# BMW_variante.net
KiCad netlist of a schematic drawn in EAGLE
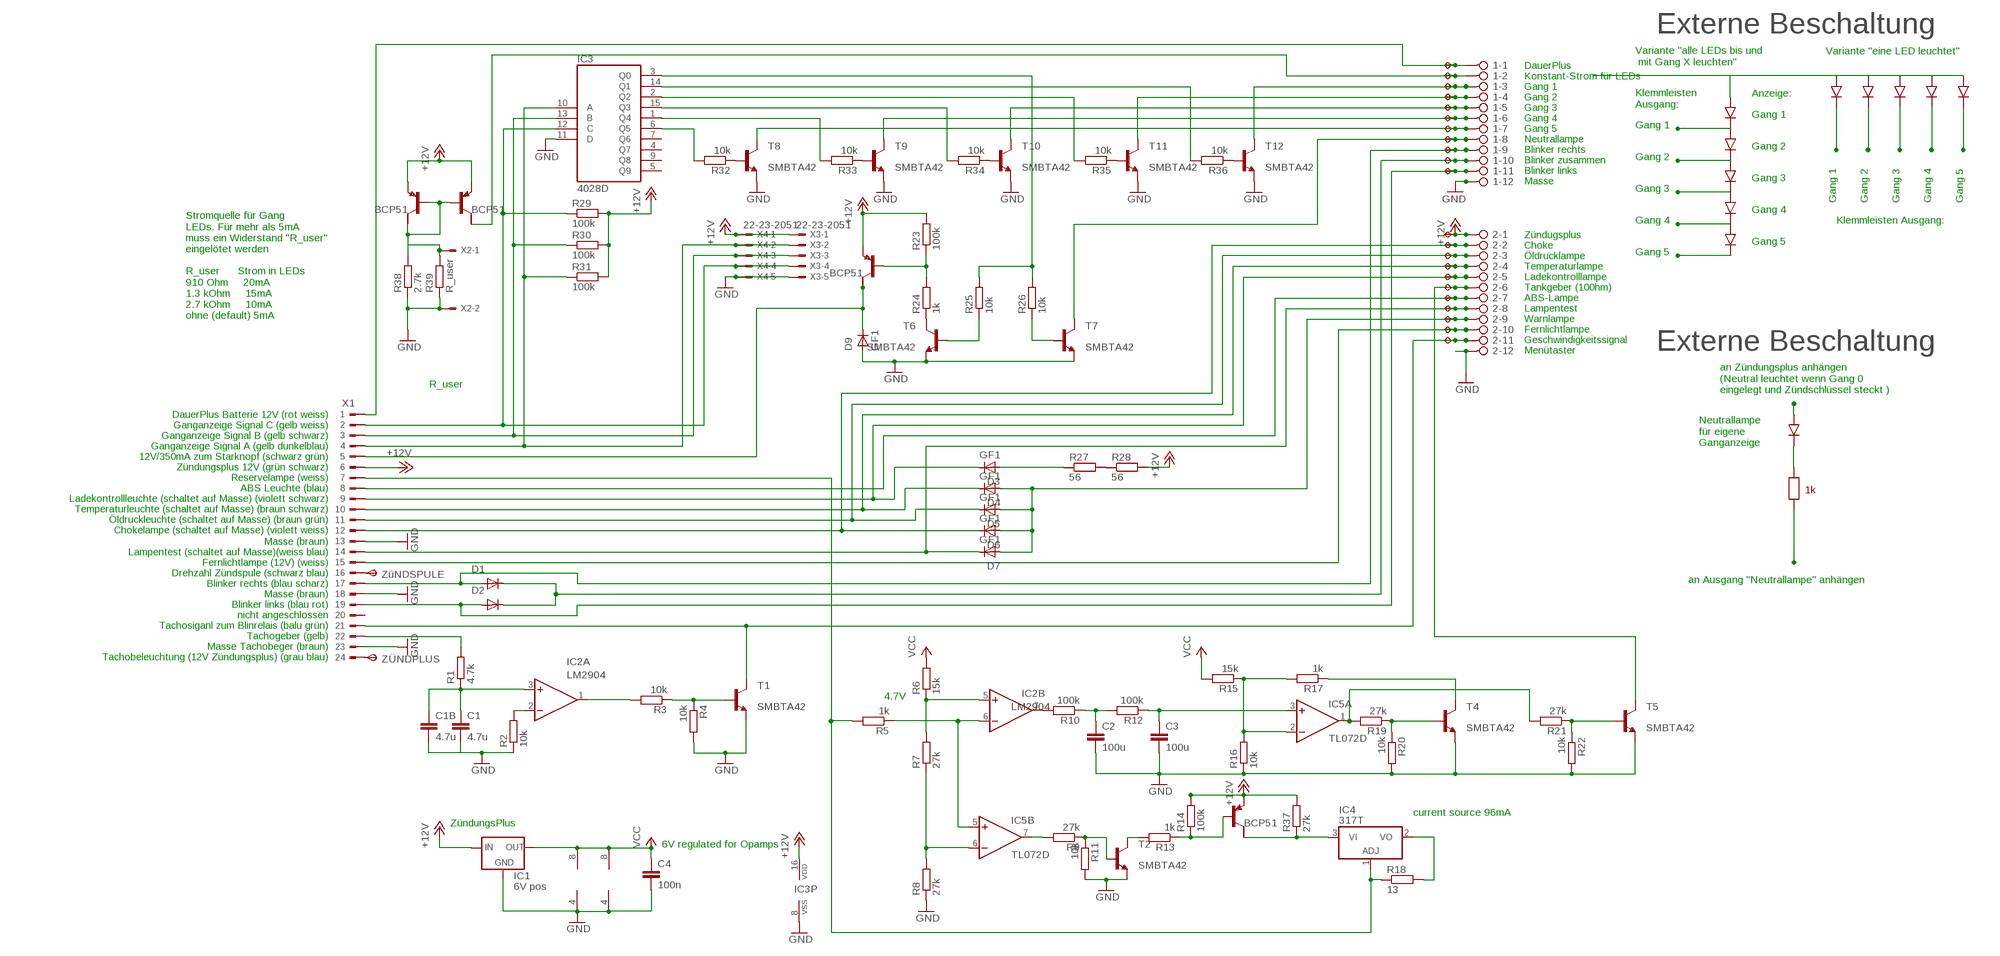
[diagram p0: schematic, sheet 1]
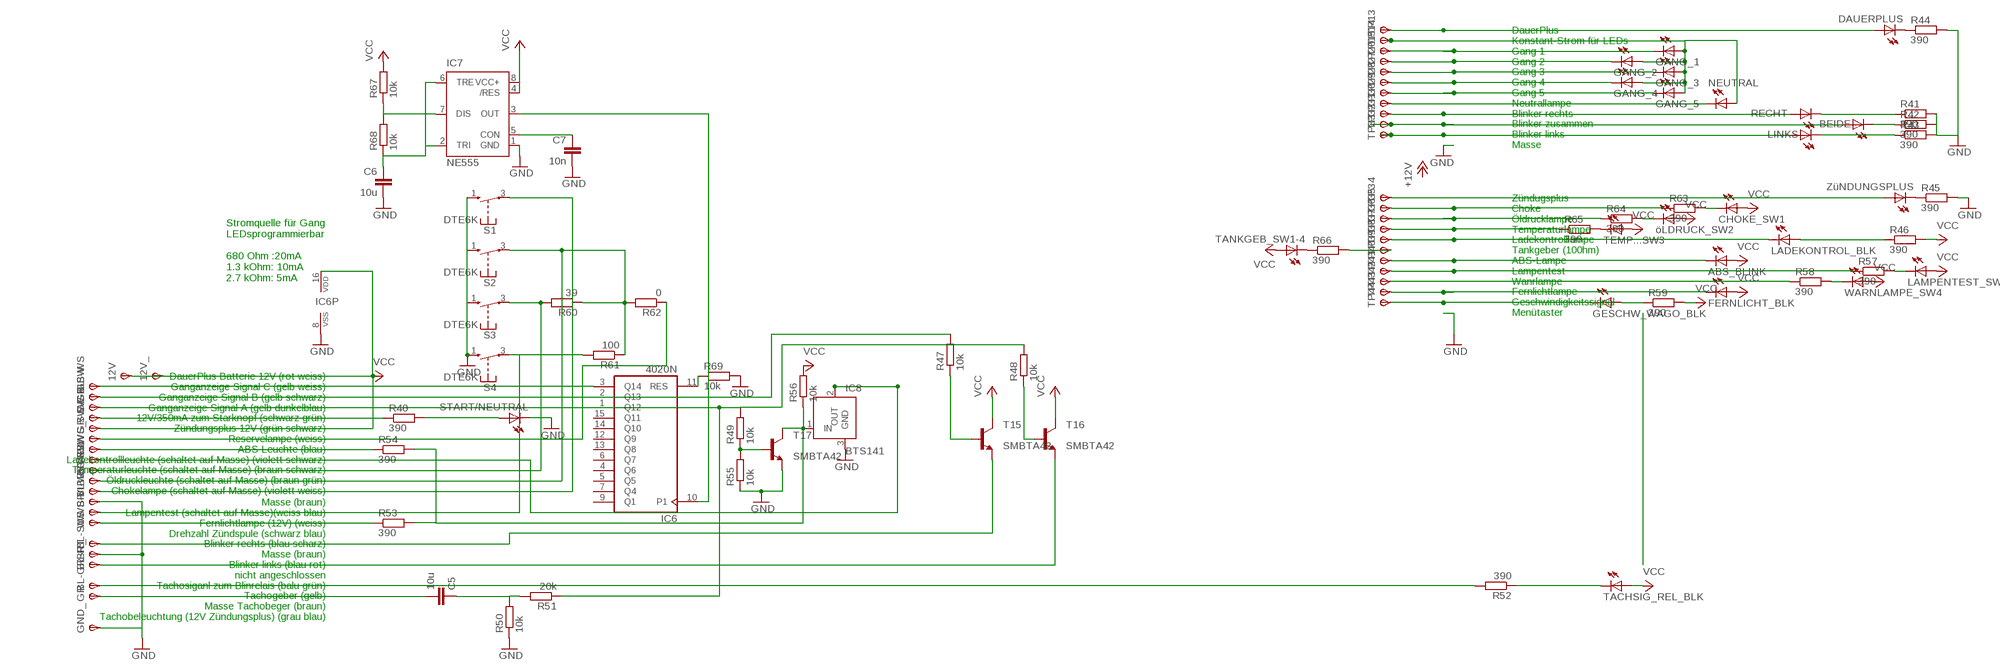
[diagram p1: schematic, sheet 2]

(export (version "E")
  (design (tool "Eeschema 10.0.6"))
  (components
    (comp (ref "1")
      (value "2081-1132")
      (footprint "eagle-import:12-PIN")
      (libsource (lib "eagle-import") (part "2081-1132"))
    )
    (comp (ref "2")
      (value "2081-1132")
      (footprint "eagle-import:12-PIN")
      (libsource (lib "eagle-import") (part "2081-1132"))
    )
    (comp (ref "C1")
      (value "4.7u")
      (footprint "eagle-import:C1206")
      (libsource (lib "eagle-import") (part "C-EUC1206"))
    )
    (comp (ref "C1B")
      (value "4.7u")
      (footprint "eagle-import:C0805K")
      (libsource (lib "eagle-import") (part "C-EUC0805K"))
    )
    (comp (ref "C2")
      (value "100u")
      (footprint "eagle-import:C1206K")
      (libsource (lib "eagle-import") (part "C-EUC1206K"))
    )
    (comp (ref "C3")
      (value "100u")
      (footprint "eagle-import:C1206K")
      (libsource (lib "eagle-import") (part "C-EUC1206K"))
    )
    (comp (ref "C4")
      (value "100n")
      (footprint "eagle-import:C1206K")
      (libsource (lib "eagle-import") (part "C-EUC1206K"))
    )
    (comp (ref "D1")
      (value "GF1")
      (footprint "eagle-import:SMA-DO214AC")
      (libsource (lib "eagle-import") (part "GF1"))
    )
    (comp (ref "D2")
      (value "GF1")
      (footprint "eagle-import:SMA-DO214AC")
      (libsource (lib "eagle-import") (part "GF1"))
    )
    (comp (ref "D3")
      (value "GF1")
      (footprint "eagle-import:SMA-DO214AC")
      (libsource (lib "eagle-import") (part "GF1"))
    )
    (comp (ref "D4")
      (value "GF1")
      (footprint "eagle-import:SMA-DO214AC")
      (libsource (lib "eagle-import") (part "GF1"))
    )
    (comp (ref "D5")
      (value "GF1")
      (footprint "eagle-import:SMA-DO214AC")
      (libsource (lib "eagle-import") (part "GF1"))
    )
    (comp (ref "D6")
      (value "GF1")
      (footprint "eagle-import:SMA-DO214AC")
      (libsource (lib "eagle-import") (part "GF1"))
    )
    (comp (ref "D7")
      (value "GF1")
      (footprint "eagle-import:SMA-DO214AC")
      (libsource (lib "eagle-import") (part "GF1"))
    )
    (comp (ref "D9")
      (value "GF1")
      (footprint "eagle-import:SMA-DO214AC")
      (libsource (lib "eagle-import") (part "GF1"))
    )
    (comp (ref "IC1")
      (value "6V pos")
      (footprint "eagle-import:78LXX")
      (libsource (lib "eagle-import") (part "78LXX"))
    )
    (comp (ref "IC2")
      (value "LM358D")
      (footprint "eagle-import:SO08")
      (fields (field (name "IC") "LM2904"))
      (libsource (lib "eagle-import") (part "LM358D"))
    )
    (comp (ref "IC3")
      (value "4028D")
      (footprint "eagle-import:SO16")
      (libsource (lib "eagle-import") (part "4028D"))
    )
    (comp (ref "IC4")
      (value "317T")
      (footprint "eagle-import:TO220H")
      (libsource (lib "eagle-import") (part "317T"))
    )
    (comp (ref "IC5")
      (value "TL072D")
      (footprint "eagle-import:SO08")
      (libsource (lib "eagle-import") (part "TL072D"))
    )
    (comp (ref "R1")
      (value "4.7k")
      (footprint "eagle-import:R0805")
      (libsource (lib "eagle-import") (part "R-EU_R0805"))
    )
    (comp (ref "R2")
      (value "10k")
      (footprint "eagle-import:R0805")
      (libsource (lib "eagle-import") (part "R-EU_R0805"))
    )
    (comp (ref "R3")
      (value "10k")
      (footprint "eagle-import:R0805")
      (libsource (lib "eagle-import") (part "R-EU_R0805"))
    )
    (comp (ref "R4")
      (value "10k")
      (footprint "eagle-import:R0805")
      (libsource (lib "eagle-import") (part "R-EU_R0805"))
    )
    (comp (ref "R5")
      (value "1k")
      (footprint "eagle-import:R0805")
      (libsource (lib "eagle-import") (part "R-EU_R0805"))
    )
    (comp (ref "R6")
      (value "15k")
      (footprint "eagle-import:R0805")
      (libsource (lib "eagle-import") (part "R-EU_R0805"))
    )
    (comp (ref "R7")
      (value "27k")
      (footprint "eagle-import:R0805")
      (libsource (lib "eagle-import") (part "R-EU_R0805"))
    )
    (comp (ref "R8")
      (value "27k")
      (footprint "eagle-import:R0805")
      (libsource (lib "eagle-import") (part "R-EU_R0805"))
    )
    (comp (ref "R9")
      (value "27k")
      (footprint "eagle-import:R0805")
      (libsource (lib "eagle-import") (part "R-EU_R0805"))
    )
    (comp (ref "R10")
      (value "100k")
      (footprint "eagle-import:R0805")
      (libsource (lib "eagle-import") (part "R-EU_R0805"))
    )
    (comp (ref "R11")
      (value "10k")
      (footprint "eagle-import:R0805")
      (libsource (lib "eagle-import") (part "R-EU_R0805"))
    )
    (comp (ref "R12")
      (value "100k")
      (footprint "eagle-import:R0805")
      (libsource (lib "eagle-import") (part "R-EU_R0805"))
    )
    (comp (ref "R13")
      (value "1k")
      (footprint "eagle-import:R0805")
      (libsource (lib "eagle-import") (part "R-EU_R0805"))
    )
    (comp (ref "R14")
      (value "100k")
      (footprint "eagle-import:R0805")
      (libsource (lib "eagle-import") (part "R-EU_R0805"))
    )
    (comp (ref "R15")
      (value "15k")
      (footprint "eagle-import:R0805")
      (libsource (lib "eagle-import") (part "R-EU_R0805"))
    )
    (comp (ref "R16")
      (value "10k")
      (footprint "eagle-import:R0805")
      (libsource (lib "eagle-import") (part "R-EU_R0805"))
    )
    (comp (ref "R17")
      (value "1k")
      (footprint "eagle-import:R0805")
      (libsource (lib "eagle-import") (part "R-EU_R0805"))
    )
    (comp (ref "R18")
      (value "13")
      (footprint "eagle-import:0207_10")
      (libsource (lib "eagle-import") (part "R-EU_0207/10"))
    )
    (comp (ref "R19")
      (value "27k")
      (footprint "eagle-import:R0805")
      (libsource (lib "eagle-import") (part "R-EU_R0805"))
    )
    (comp (ref "R20")
      (value "10k")
      (footprint "eagle-import:R0805")
      (libsource (lib "eagle-import") (part "R-EU_R0805"))
    )
    (comp (ref "R21")
      (value "27k")
      (footprint "eagle-import:R0805")
      (libsource (lib "eagle-import") (part "R-EU_R0805"))
    )
    (comp (ref "R22")
      (value "10k")
      (footprint "eagle-import:R0805")
      (libsource (lib "eagle-import") (part "R-EU_R0805"))
    )
    (comp (ref "R23")
      (value "100k")
      (footprint "eagle-import:R0805")
      (libsource (lib "eagle-import") (part "R-EU_R0805"))
    )
    (comp (ref "R24")
      (value "1k")
      (footprint "eagle-import:R0805")
      (libsource (lib "eagle-import") (part "R-EU_R0805"))
    )
    (comp (ref "R25")
      (value "10k")
      (footprint "eagle-import:R0805")
      (libsource (lib "eagle-import") (part "R-EU_R0805"))
    )
    (comp (ref "R26")
      (value "10k")
      (footprint "eagle-import:R0805")
      (libsource (lib "eagle-import") (part "R-EU_R0805"))
    )
    (comp (ref "R27")
      (value "56")
      (footprint "eagle-import:V235_17")
      (libsource (lib "eagle-import") (part "R-EU_V235/17"))
    )
    (comp (ref "R28")
      (value "56")
      (footprint "eagle-import:V235_17")
      (libsource (lib "eagle-import") (part "R-EU_V235/17"))
    )
    (comp (ref "R29")
      (value "100k")
      (footprint "eagle-import:R0805")
      (libsource (lib "eagle-import") (part "R-EU_R0805"))
    )
    (comp (ref "R30")
      (value "100k")
      (footprint "eagle-import:R0805")
      (libsource (lib "eagle-import") (part "R-EU_R0805"))
    )
    (comp (ref "R31")
      (value "100k")
      (footprint "eagle-import:R0805")
      (libsource (lib "eagle-import") (part "R-EU_R0805"))
    )
    (comp (ref "R32")
      (value "10k")
      (footprint "eagle-import:R0805")
      (libsource (lib "eagle-import") (part "R-EU_R0805"))
    )
    (comp (ref "R33")
      (value "10k")
      (footprint "eagle-import:R0805")
      (libsource (lib "eagle-import") (part "R-EU_R0805"))
    )
    (comp (ref "R34")
      (value "10k")
      (footprint "eagle-import:R0805")
      (libsource (lib "eagle-import") (part "R-EU_R0805"))
    )
    (comp (ref "R35")
      (value "10k")
      (footprint "eagle-import:R0805")
      (libsource (lib "eagle-import") (part "R-EU_R0805"))
    )
    (comp (ref "R36")
      (value "10k")
      (footprint "eagle-import:R0805")
      (libsource (lib "eagle-import") (part "R-EU_R0805"))
    )
    (comp (ref "R37")
      (value "27k")
      (footprint "eagle-import:R0805")
      (libsource (lib "eagle-import") (part "R-EU_R0805"))
    )
    (comp (ref "R38")
      (value "2.7k")
      (footprint "eagle-import:R0805")
      (libsource (lib "eagle-import") (part "R-EU_R0805"))
    )
    (comp (ref "R39")
      (value "R_user")
      (footprint "eagle-import:R0805")
      (libsource (lib "eagle-import") (part "R-EU_R0805"))
    )
    (comp (ref "T")
      (value "BCP53T1")
      (footprint "eagle-import:SOT223")
      (fields (field (name "T") "BCP51"))
      (libsource (lib "eagle-import") (part "BCP53T1"))
    )
    (comp (ref "T1")
      (value "MMBTA42LT1-NPN-SOT23-BEC")
      (footprint "eagle-import:SOT23-BEC")
      (fields (field (name "T") "SMBTA42"))
      (libsource (lib "eagle-import") (part "-NPN-SOT23-BECMMBTA42LT1"))
    )
    (comp (ref "T2")
      (value "MMBTA42LT1-NPN-SOT23-BEC")
      (footprint "eagle-import:SOT23-BEC")
      (fields (field (name "T") "SMBTA42"))
      (libsource (lib "eagle-import") (part "-NPN-SOT23-BECMMBTA42LT1"))
    )
    (comp (ref "T3")
      (value "BCP53T1")
      (footprint "eagle-import:SOT223")
      (fields (field (name "T") "BCP51"))
      (libsource (lib "eagle-import") (part "BCP53T1"))
    )
    (comp (ref "T4")
      (value "MMBTA42LT1-NPN-SOT23-BEC")
      (footprint "eagle-import:SOT23-BEC")
      (fields (field (name "T") "SMBTA42"))
      (libsource (lib "eagle-import") (part "-NPN-SOT23-BECMMBTA42LT1"))
    )
    (comp (ref "T5")
      (value "MMBTA42LT1-NPN-SOT23-BEC")
      (footprint "eagle-import:SOT23-BEC")
      (fields (field (name "T") "SMBTA42"))
      (libsource (lib "eagle-import") (part "-NPN-SOT23-BECMMBTA42LT1"))
    )
    (comp (ref "T6")
      (value "MMBTA42LT1-NPN-SOT23-BEC")
      (footprint "eagle-import:SOT23-BEC")
      (fields (field (name "T") "SMBTA42"))
      (libsource (lib "eagle-import") (part "-NPN-SOT23-BECMMBTA42LT1"))
    )
    (comp (ref "T7")
      (value "MMBTA42LT1-NPN-SOT23-BEC")
      (footprint "eagle-import:SOT23-BEC")
      (fields (field (name "T") "SMBTA42"))
      (libsource (lib "eagle-import") (part "-NPN-SOT23-BECMMBTA42LT1"))
    )
    (comp (ref "T8")
      (value "MMBTA42LT1-NPN-SOT23-BEC")
      (footprint "eagle-import:SOT23-BEC")
      (fields (field (name "T") "SMBTA42"))
      (libsource (lib "eagle-import") (part "-NPN-SOT23-BECMMBTA42LT1"))
    )
    (comp (ref "T9")
      (value "MMBTA42LT1-NPN-SOT23-BEC")
      (footprint "eagle-import:SOT23-BEC")
      (fields (field (name "T") "SMBTA42"))
      (libsource (lib "eagle-import") (part "-NPN-SOT23-BECMMBTA42LT1"))
    )
    (comp (ref "T10")
      (value "MMBTA42LT1-NPN-SOT23-BEC")
      (footprint "eagle-import:SOT23-BEC")
      (fields (field (name "T") "SMBTA42"))
      (libsource (lib "eagle-import") (part "-NPN-SOT23-BECMMBTA42LT1"))
    )
    (comp (ref "T11")
      (value "MMBTA42LT1-NPN-SOT23-BEC")
      (footprint "eagle-import:SOT23-BEC")
      (fields (field (name "T") "SMBTA42"))
      (libsource (lib "eagle-import") (part "-NPN-SOT23-BECMMBTA42LT1"))
    )
    (comp (ref "T12")
      (value "MMBTA42LT1-NPN-SOT23-BEC")
      (footprint "eagle-import:SOT23-BEC")
      (fields (field (name "T") "SMBTA42"))
      (libsource (lib "eagle-import") (part "-NPN-SOT23-BECMMBTA42LT1"))
    )
    (comp (ref "T13")
      (value "BCP53T1")
      (footprint "eagle-import:SOT223")
      (fields (field (name "T") "BCP51"))
      (libsource (lib "eagle-import") (part "BCP53T1"))
    )
    (comp (ref "T14")
      (value "BCP53T1")
      (footprint "eagle-import:SOT223")
      (fields (field (name "T") "BCP51"))
      (libsource (lib "eagle-import") (part "BCP53T1"))
    )
    (comp (ref "TP1")
      (value "TPB1,27")
      (footprint "eagle-import:B1,27")
      (libsource (lib "eagle-import") (part "TPB1,27"))
    )
    (comp (ref "TP2")
      (value "TPB1,27")
      (footprint "eagle-import:B1,27")
      (libsource (lib "eagle-import") (part "TPB1,27"))
    )
    (comp (ref "TP3")
      (value "TPB1,27")
      (footprint "eagle-import:B1,27")
      (libsource (lib "eagle-import") (part "TPB1,27"))
    )
    (comp (ref "TP4")
      (value "TPB1,27")
      (footprint "eagle-import:B1,27")
      (libsource (lib "eagle-import") (part "TPB1,27"))
    )
    (comp (ref "TP5")
      (value "TPB1,27")
      (footprint "eagle-import:B1,27")
      (libsource (lib "eagle-import") (part "TPB1,27"))
    )
    (comp (ref "TP6")
      (value "TPB1,27")
      (footprint "eagle-import:B1,27")
      (libsource (lib "eagle-import") (part "TPB1,27"))
    )
    (comp (ref "TP7")
      (value "TPB1,27")
      (footprint "eagle-import:B1,27")
      (libsource (lib "eagle-import") (part "TPB1,27"))
    )
    (comp (ref "TP8")
      (value "TPB1,27")
      (footprint "eagle-import:B1,27")
      (libsource (lib "eagle-import") (part "TPB1,27"))
    )
    (comp (ref "TP9")
      (value "TPB1,27")
      (footprint "eagle-import:B1,27")
      (libsource (lib "eagle-import") (part "TPB1,27"))
    )
    (comp (ref "TP10")
      (value "TPB1,27")
      (footprint "eagle-import:B1,27")
      (libsource (lib "eagle-import") (part "TPB1,27"))
    )
    (comp (ref "TP11")
      (value "TPB1,27")
      (footprint "eagle-import:B1,27")
      (libsource (lib "eagle-import") (part "TPB1,27"))
    )
    (comp (ref "TP12")
      (value "TPB1,27")
      (footprint "eagle-import:B1,27")
      (libsource (lib "eagle-import") (part "TPB1,27"))
    )
    (comp (ref "TP16")
      (value "TPB1,27")
      (footprint "eagle-import:B1,27")
      (libsource (lib "eagle-import") (part "TPB1,27"))
    )
    (comp (ref "TP17")
      (value "TPB1,27")
      (footprint "eagle-import:B1,27")
      (libsource (lib "eagle-import") (part "TPB1,27"))
    )
    (comp (ref "TP18")
      (value "TPB1,27")
      (footprint "eagle-import:B1,27")
      (libsource (lib "eagle-import") (part "TPB1,27"))
    )
    (comp (ref "TP19")
      (value "TPB1,27")
      (footprint "eagle-import:B1,27")
      (libsource (lib "eagle-import") (part "TPB1,27"))
    )
    (comp (ref "TP21")
      (value "TPB1,27")
      (footprint "eagle-import:B1,27")
      (libsource (lib "eagle-import") (part "TPB1,27"))
    )
    (comp (ref "TP22")
      (value "TPB1,27")
      (footprint "eagle-import:B1,27")
      (libsource (lib "eagle-import") (part "TPB1,27"))
    )
    (comp (ref "TP23")
      (value "TPB1,27")
      (footprint "eagle-import:B1,27")
      (libsource (lib "eagle-import") (part "TPB1,27"))
    )
    (comp (ref "TP24")
      (value "TPB1,27")
      (footprint "eagle-import:B1,27")
      (libsource (lib "eagle-import") (part "TPB1,27"))
    )
    (comp (ref "TP25")
      (value "TPB1,27")
      (footprint "eagle-import:B1,27")
      (libsource (lib "eagle-import") (part "TPB1,27"))
    )
    (comp (ref "TP26")
      (value "TPB1,27")
      (footprint "eagle-import:B1,27")
      (libsource (lib "eagle-import") (part "TPB1,27"))
    )
    (comp (ref "X1")
      (value "CON_BMW")
      (footprint "eagle-import:24-PIN")
      (libsource (lib "eagle-import") (part "CON_BMW"))
    )
    (comp (ref "X2")
      (value "22-23-2021")
      (footprint "eagle-import:22-23-2021")
      (fields (field (name "MF") "MOLEX"))
      (libsource (lib "eagle-import") (part "22-23-2021"))
    )
    (comp (ref "X3")
      (value "22-23-2051")
      (footprint "eagle-import:22-23-2051")
      (fields (field (name "MF") "MOLEX"))
      (libsource (lib "eagle-import") (part "22-23-2051"))
    )
    (comp (ref "X4")
      (value "22-23-2051")
      (footprint "eagle-import:22-23-2051")
      (fields (field (name "MF") "MOLEX"))
      (libsource (lib "eagle-import") (part "22-23-2051"))
    )
    (comp (ref "ZÜNDPLUS")
      (value "TPSP1_1MM")
      (footprint "eagle-import:P1_1.0MM")
      (libsource (lib "eagle-import") (part "TPSP1_1MM"))
    )
    (comp (ref "ZüNDSPULE")
      (value "TPSP1_1MM")
      (footprint "eagle-import:P1_1.0MM")
      (libsource (lib "eagle-import") (part "TPSP1_1MM"))
    )
    (comp (ref "12V")
      (value "TPSPAD1-1.5MM")
      (footprint "eagle-import:P1-13")
      (libsource (lib "eagle-import") (part "TPSPAD1-1.5MM"))
    )
    (comp (ref "12V_")
      (value "TPSPAD1-1.5MM")
      (footprint "eagle-import:P1-13")
      (libsource (lib "eagle-import") (part "TPSPAD1-1.5MM"))
    )
    (comp (ref "ABS_BLINK")
      (value "TLLY4400")
      (footprint "eagle-import:LED3MM")
      (fields (field (name "MF") "VISHAY SEMICONDUCTOR"))
      (libsource (lib "eagle-import") (part "TLLY4400"))
    )
    (comp (ref "BEIDE")
      (value "TLLY4400")
      (footprint "eagle-import:LED3MM")
      (fields (field (name "MF") "VISHAY SEMICONDUCTOR"))
      (libsource (lib "eagle-import") (part "TLLY4400"))
    )
    (comp (ref "BL")
      (value "TPSPAD1-1.5MM")
      (footprint "eagle-import:P1-13")
      (libsource (lib "eagle-import") (part "TPSPAD1-1.5MM"))
    )
    (comp (ref "BL-GR")
      (value "TPSPAD1-1.5MM")
      (footprint "eagle-import:P1-13")
      (libsource (lib "eagle-import") (part "TPSPAD1-1.5MM"))
    )
    (comp (ref "BL-RT")
      (value "TPSPAD1-1.5MM")
      (footprint "eagle-import:P1-13")
      (libsource (lib "eagle-import") (part "TPSPAD1-1.5MM"))
    )
    (comp (ref "BL-SW")
      (value "TPSPAD1-1.5MM")
      (footprint "eagle-import:P1-13")
      (libsource (lib "eagle-import") (part "TPSPAD1-1.5MM"))
    )
    (comp (ref "BR")
      (value "TPSPAD1-1.5MM")
      (footprint "eagle-import:P1-13")
      (libsource (lib "eagle-import") (part "TPSPAD1-1.5MM"))
    )
    (comp (ref "BR-GR")
      (value "TPSPAD1-1.5MM")
      (footprint "eagle-import:P1-13")
      (libsource (lib "eagle-import") (part "TPSPAD1-1.5MM"))
    )
    (comp (ref "BR-SW")
      (value "TPSPAD1-1.5MM")
      (footprint "eagle-import:P1-13")
      (libsource (lib "eagle-import") (part "TPSPAD1-1.5MM"))
    )
    (comp (ref "BR_")
      (value "TPSPAD1-1.5MM")
      (footprint "eagle-import:P1-13")
      (libsource (lib "eagle-import") (part "TPSPAD1-1.5MM"))
    )
    (comp (ref "C5")
      (value "10u")
      (footprint "eagle-import:C025-024X044")
      (libsource (lib "eagle-import") (part "C-EU025-024X044"))
    )
    (comp (ref "C6")
      (value "10u")
      (footprint "eagle-import:C025-024X044")
      (libsource (lib "eagle-import") (part "C-EU025-024X044"))
    )
    (comp (ref "C7")
      (value "10n")
      (footprint "eagle-import:C025-024X044")
      (libsource (lib "eagle-import") (part "C-EU025-024X044"))
    )
    (comp (ref "CHOKE_SW1")
      (value "TLLY4400")
      (footprint "eagle-import:LED3MM")
      (fields (field (name "MF") "VISHAY SEMICONDUCTOR"))
      (libsource (lib "eagle-import") (part "TLLY4400"))
    )
    (comp (ref "DAUERPLUS")
      (value "TLLY4400")
      (footprint "eagle-import:LED3MM")
      (fields (field (name "MF") "VISHAY SEMICONDUCTOR"))
      (libsource (lib "eagle-import") (part "TLLY4400"))
    )
    (comp (ref "FERNLICHT_BLK")
      (value "TLLY4400")
      (footprint "eagle-import:LED3MM")
      (fields (field (name "MF") "VISHAY SEMICONDUCTOR"))
      (libsource (lib "eagle-import") (part "TLLY4400"))
    )
    (comp (ref "GANG_1")
      (value "TLLY4400")
      (footprint "eagle-import:LED3MM")
      (fields (field (name "MF") "VISHAY SEMICONDUCTOR"))
      (libsource (lib "eagle-import") (part "TLLY4400"))
    )
    (comp (ref "GANG_2")
      (value "TLLY4400")
      (footprint "eagle-import:LED3MM")
      (fields (field (name "MF") "VISHAY SEMICONDUCTOR"))
      (libsource (lib "eagle-import") (part "TLLY4400"))
    )
    (comp (ref "GANG_3")
      (value "TLLY4400")
      (footprint "eagle-import:LED3MM")
      (fields (field (name "MF") "VISHAY SEMICONDUCTOR"))
      (libsource (lib "eagle-import") (part "TLLY4400"))
    )
    (comp (ref "GANG_4")
      (value "TLLY4400")
      (footprint "eagle-import:LED3MM")
      (fields (field (name "MF") "VISHAY SEMICONDUCTOR"))
      (libsource (lib "eagle-import") (part "TLLY4400"))
    )
    (comp (ref "GANG_5")
      (value "TLLY4400")
      (footprint "eagle-import:LED3MM")
      (fields (field (name "MF") "VISHAY SEMICONDUCTOR"))
      (libsource (lib "eagle-import") (part "TLLY4400"))
    )
    (comp (ref "GB-SW")
      (value "TPSPAD1-1.5MM")
      (footprint "eagle-import:P1-13")
      (libsource (lib "eagle-import") (part "TPSPAD1-1.5MM"))
    )
    (comp (ref "GB-WS")
      (value "TPSPAD1-1.5MM")
      (footprint "eagle-import:P1-13")
      (libsource (lib "eagle-import") (part "TPSPAD1-1.5MM"))
    )
    (comp (ref "GE-BL")
      (value "TPSPAD1-1.5MM")
      (footprint "eagle-import:P1-13")
      (libsource (lib "eagle-import") (part "TPSPAD1-1.5MM"))
    )
    (comp (ref "GESCHW_WAGO_BLK")
      (value "TLLY4400")
      (footprint "eagle-import:LED3MM")
      (fields (field (name "MF") "VISHAY SEMICONDUCTOR"))
      (libsource (lib "eagle-import") (part "TLLY4400"))
    )
    (comp (ref "GND_")
      (value "TPSPAD1-1.5MM")
      (footprint "eagle-import:P1-13")
      (libsource (lib "eagle-import") (part "TPSPAD1-1.5MM"))
    )
    (comp (ref "GR")
      (value "TPSPAD1-1.5MM")
      (footprint "eagle-import:P1-13")
      (libsource (lib "eagle-import") (part "TPSPAD1-1.5MM"))
    )
    (comp (ref "GR-SW")
      (value "TPSPAD1-1.5MM")
      (footprint "eagle-import:P1-13")
      (libsource (lib "eagle-import") (part "TPSPAD1-1.5MM"))
    )
    (comp (ref "IC6")
      (value "4020N")
      (footprint "eagle-import:DIL16")
      (libsource (lib "eagle-import") (part "4020N"))
    )
    (comp (ref "IC7")
      (value "NE555")
      (footprint "eagle-import:DIL-08")
      (fields (field (name "MF") "Arrow Electronics") (field (name "MPN") "NE555N"))
      (libsource (lib "eagle-import") (part "NE555"))
    )
    (comp (ref "IC8")
      (value "BTS141")
      (footprint "eagle-import:TO220-3-45")
      (libsource (lib "eagle-import") (part "BTS141"))
    )
    (comp (ref "LADEKONTROL_BLK")
      (value "TLLY4400")
      (footprint "eagle-import:LED3MM")
      (fields (field (name "MF") "VISHAY SEMICONDUCTOR"))
      (libsource (lib "eagle-import") (part "TLLY4400"))
    )
    (comp (ref "LAMPENTEST_SW4")
      (value "TLLY4400")
      (footprint "eagle-import:LED3MM")
      (fields (field (name "MF") "VISHAY SEMICONDUCTOR"))
      (libsource (lib "eagle-import") (part "TLLY4400"))
    )
    (comp (ref "LINKS")
      (value "TLLY4400")
      (footprint "eagle-import:LED3MM")
      (fields (field (name "MF") "VISHAY SEMICONDUCTOR"))
      (libsource (lib "eagle-import") (part "TLLY4400"))
    )
    (comp (ref "NEUTRAL")
      (value "TLLY4400")
      (footprint "eagle-import:LED3MM")
      (fields (field (name "MF") "VISHAY SEMICONDUCTOR"))
      (libsource (lib "eagle-import") (part "TLLY4400"))
    )
    (comp (ref "R40")
      (value "390")
      (footprint "eagle-import:R0805")
      (libsource (lib "eagle-import") (part "R-EU_R0805"))
    )
    (comp (ref "R41")
      (value "390")
      (footprint "eagle-import:R0805")
      (libsource (lib "eagle-import") (part "R-EU_R0805"))
    )
    (comp (ref "R42")
      (value "390")
      (footprint "eagle-import:R0805")
      (libsource (lib "eagle-import") (part "R-EU_R0805"))
    )
    (comp (ref "R43")
      (value "390")
      (footprint "eagle-import:R0805")
      (libsource (lib "eagle-import") (part "R-EU_R0805"))
    )
    (comp (ref "R44")
      (value "390")
      (footprint "eagle-import:R0805")
      (libsource (lib "eagle-import") (part "R-EU_R0805"))
    )
    (comp (ref "R45")
      (value "390")
      (footprint "eagle-import:R0805")
      (libsource (lib "eagle-import") (part "R-EU_R0805"))
    )
    (comp (ref "R46")
      (value "390")
      (footprint "eagle-import:R0805")
      (libsource (lib "eagle-import") (part "R-EU_R0805"))
    )
    (comp (ref "R47")
      (value "10k")
      (footprint "eagle-import:R0805")
      (libsource (lib "eagle-import") (part "R-EU_R0805"))
    )
    (comp (ref "R48")
      (value "10k")
      (footprint "eagle-import:R0805")
      (libsource (lib "eagle-import") (part "R-EU_R0805"))
    )
    (comp (ref "R49")
      (value "10k")
      (footprint "eagle-import:R0805")
      (libsource (lib "eagle-import") (part "R-EU_R0805"))
    )
    (comp (ref "R50")
      (value "10k")
      (footprint "eagle-import:0207_12")
      (libsource (lib "eagle-import") (part "R-EU_0207/12"))
    )
    (comp (ref "R51")
      (value "20k")
      (footprint "eagle-import:0207_12")
      (libsource (lib "eagle-import") (part "R-EU_0207/12"))
    )
    (comp (ref "R52")
      (value "390")
      (footprint "eagle-import:R0805")
      (libsource (lib "eagle-import") (part "R-EU_R0805"))
    )
    (comp (ref "R53")
      (value "390")
      (footprint "eagle-import:R0805")
      (libsource (lib "eagle-import") (part "R-EU_R0805"))
    )
    (comp (ref "R54")
      (value "390")
      (footprint "eagle-import:R0805")
      (libsource (lib "eagle-import") (part "R-EU_R0805"))
    )
    (comp (ref "R55")
      (value "10k")
      (footprint "eagle-import:R0805")
      (libsource (lib "eagle-import") (part "R-EU_R0805"))
    )
    (comp (ref "R56")
      (value "10k")
      (footprint "eagle-import:R0805")
      (libsource (lib "eagle-import") (part "R-EU_R0805"))
    )
    (comp (ref "R57")
      (value "390")
      (footprint "eagle-import:R0805")
      (libsource (lib "eagle-import") (part "R-EU_R0805"))
    )
    (comp (ref "R58")
      (value "390")
      (footprint "eagle-import:R0805")
      (libsource (lib "eagle-import") (part "R-EU_R0805"))
    )
    (comp (ref "R59")
      (value "390")
      (footprint "eagle-import:R0805")
      (libsource (lib "eagle-import") (part "R-EU_R0805"))
    )
    (comp (ref "R60")
      (value "39")
      (footprint "eagle-import:0207_12")
      (libsource (lib "eagle-import") (part "R-EU_0207/12"))
    )
    (comp (ref "R61")
      (value "100")
      (footprint "eagle-import:0207_12")
      (libsource (lib "eagle-import") (part "R-EU_0207/12"))
    )
    (comp (ref "R62")
      (value "0")
      (footprint "eagle-import:0207_12")
      (libsource (lib "eagle-import") (part "R-EU_0207/12"))
    )
    (comp (ref "R63")
      (value "390")
      (footprint "eagle-import:R0805")
      (libsource (lib "eagle-import") (part "R-EU_R0805"))
    )
    (comp (ref "R64")
      (value "390")
      (footprint "eagle-import:R0805")
      (libsource (lib "eagle-import") (part "R-EU_R0805"))
    )
    (comp (ref "R65")
      (value "390")
      (footprint "eagle-import:R0805")
      (libsource (lib "eagle-import") (part "R-EU_R0805"))
    )
    (comp (ref "R66")
      (value "390")
      (footprint "eagle-import:R0805")
      (libsource (lib "eagle-import") (part "R-EU_R0805"))
    )
    (comp (ref "R67")
      (value "10k")
      (footprint "eagle-import:0207_12")
      (libsource (lib "eagle-import") (part "R-EU_0207/12"))
    )
    (comp (ref "R68")
      (value "10k")
      (footprint "eagle-import:0207_15")
      (libsource (lib "eagle-import") (part "R-EU_0207/15"))
    )
    (comp (ref "R69")
      (value "10k")
      (footprint "eagle-import:R0805")
      (libsource (lib "eagle-import") (part "R-EU_R0805"))
    )
    (comp (ref "RECHT")
      (value "TLLY4400")
      (footprint "eagle-import:LED3MM")
      (fields (field (name "MF") "VISHAY SEMICONDUCTOR"))
      (libsource (lib "eagle-import") (part "TLLY4400"))
    )
    (comp (ref "S1")
      (value "DTE6K")
      (footprint "eagle-import:DTE6K")
      (libsource (lib "eagle-import") (part "DTE6K"))
    )
    (comp (ref "S2")
      (value "DTE6K")
      (footprint "eagle-import:DTE6K")
      (libsource (lib "eagle-import") (part "DTE6K"))
    )
    (comp (ref "S3")
      (value "DTE6K")
      (footprint "eagle-import:DTE6K")
      (libsource (lib "eagle-import") (part "DTE6K"))
    )
    (comp (ref "S4")
      (value "DTE6K")
      (footprint "eagle-import:DTE6K")
      (libsource (lib "eagle-import") (part "DTE6K"))
    )
    (comp (ref "START/NEUTRAL")
      (value "TLLY4400")
      (footprint "eagle-import:LED3MM")
      (fields (field (name "MF") "VISHAY SEMICONDUCTOR"))
      (libsource (lib "eagle-import") (part "TLLY4400"))
    )
    (comp (ref "SW-GR")
      (value "TPSPAD1-1.5MM")
      (footprint "eagle-import:P1-13")
      (libsource (lib "eagle-import") (part "TPSPAD1-1.5MM"))
    )
    (comp (ref "T15")
      (value "MMBTA42LT1-NPN-SOT23-BEC")
      (footprint "eagle-import:SOT23-BEC")
      (fields (field (name "T") "SMBTA42"))
      (libsource (lib "eagle-import") (part "-NPN-SOT23-BECMMBTA42LT1"))
    )
    (comp (ref "T16")
      (value "MMBTA42LT1-NPN-SOT23-BEC")
      (footprint "eagle-import:SOT23-BEC")
      (fields (field (name "T") "SMBTA42"))
      (libsource (lib "eagle-import") (part "-NPN-SOT23-BECMMBTA42LT1"))
    )
    (comp (ref "T17")
      (value "MMBTA42LT1-NPN-SOT23-BEC")
      (footprint "eagle-import:SOT23-BEC")
      (fields (field (name "T") "SMBTA42"))
      (libsource (lib "eagle-import") (part "-NPN-SOT23-BECMMBTA42LT1"))
    )
    (comp (ref "TACHSIG_REL_BLK")
      (value "TLLY4400")
      (footprint "eagle-import:LED3MM")
      (fields (field (name "MF") "VISHAY SEMICONDUCTOR"))
      (libsource (lib "eagle-import") (part "TLLY4400"))
    )
    (comp (ref "TANKGEB_SW1-4")
      (value "TLLY4400")
      (footprint "eagle-import:LED3MM")
      (fields (field (name "MF") "VISHAY SEMICONDUCTOR"))
      (libsource (lib "eagle-import") (part "TLLY4400"))
    )
    (comp (ref "TEMP...SW3")
      (value "TLLY4400")
      (footprint "eagle-import:LED3MM")
      (fields (field (name "MF") "VISHAY SEMICONDUCTOR"))
      (libsource (lib "eagle-import") (part "TLLY4400"))
    )
    (comp (ref "TP13")
      (value "TPSPAD1-1.5MM")
      (footprint "eagle-import:P1-13")
      (libsource (lib "eagle-import") (part "TPSPAD1-1.5MM"))
    )
    (comp (ref "TP14")
      (value "TPSPAD1-1.5MM")
      (footprint "eagle-import:P1-13")
      (libsource (lib "eagle-import") (part "TPSPAD1-1.5MM"))
    )
    (comp (ref "TP15")
      (value "TPSPAD1-1.5MM")
      (footprint "eagle-import:P1-13")
      (libsource (lib "eagle-import") (part "TPSPAD1-1.5MM"))
    )
    (comp (ref "TP20")
      (value "TPSPAD1-1.5MM")
      (footprint "eagle-import:P1-13")
      (libsource (lib "eagle-import") (part "TPSPAD1-1.5MM"))
    )
    (comp (ref "TP27")
      (value "TPSPAD1-1.5MM")
      (footprint "eagle-import:P1-13")
      (libsource (lib "eagle-import") (part "TPSPAD1-1.5MM"))
    )
    (comp (ref "TP28")
      (value "TPSPAD1-1.5MM")
      (footprint "eagle-import:P1-13")
      (libsource (lib "eagle-import") (part "TPSPAD1-1.5MM"))
    )
    (comp (ref "TP29")
      (value "TPSPAD1-1.5MM")
      (footprint "eagle-import:P1-13")
      (libsource (lib "eagle-import") (part "TPSPAD1-1.5MM"))
    )
    (comp (ref "TP30")
      (value "TPSPAD1-1.5MM")
      (footprint "eagle-import:P1-13")
      (libsource (lib "eagle-import") (part "TPSPAD1-1.5MM"))
    )
    (comp (ref "TP31")
      (value "TPSPAD1-1.5MM")
      (footprint "eagle-import:P1-13")
      (libsource (lib "eagle-import") (part "TPSPAD1-1.5MM"))
    )
    (comp (ref "TP32")
      (value "TPSPAD1-1.5MM")
      (footprint "eagle-import:P1-13")
      (libsource (lib "eagle-import") (part "TPSPAD1-1.5MM"))
    )
    (comp (ref "TP33")
      (value "TPSPAD1-1.5MM")
      (footprint "eagle-import:P1-13")
      (libsource (lib "eagle-import") (part "TPSPAD1-1.5MM"))
    )
    (comp (ref "TP34")
      (value "TPSPAD1-1.5MM")
      (footprint "eagle-import:P1-13")
      (libsource (lib "eagle-import") (part "TPSPAD1-1.5MM"))
    )
    (comp (ref "TP35")
      (value "TPSPAD1-1.5MM")
      (footprint "eagle-import:P1-13")
      (libsource (lib "eagle-import") (part "TPSPAD1-1.5MM"))
    )
    (comp (ref "TP36")
      (value "TPSPAD1-1.5MM")
      (footprint "eagle-import:P1-13")
      (libsource (lib "eagle-import") (part "TPSPAD1-1.5MM"))
    )
    (comp (ref "TP37")
      (value "TPSPAD1-1.5MM")
      (footprint "eagle-import:P1-13")
      (libsource (lib "eagle-import") (part "TPSPAD1-1.5MM"))
    )
    (comp (ref "TP38")
      (value "TPSPAD1-1.5MM")
      (footprint "eagle-import:P1-13")
      (libsource (lib "eagle-import") (part "TPSPAD1-1.5MM"))
    )
    (comp (ref "TP39")
      (value "TPSPAD1-1.5MM")
      (footprint "eagle-import:P1-13")
      (libsource (lib "eagle-import") (part "TPSPAD1-1.5MM"))
    )
    (comp (ref "TP40")
      (value "TPSPAD1-1.5MM")
      (footprint "eagle-import:P1-13")
      (libsource (lib "eagle-import") (part "TPSPAD1-1.5MM"))
    )
    (comp (ref "TP41")
      (value "TPSPAD1-1.5MM")
      (footprint "eagle-import:P1-13")
      (libsource (lib "eagle-import") (part "TPSPAD1-1.5MM"))
    )
    (comp (ref "TP42")
      (value "TPSPAD1-1.5MM")
      (footprint "eagle-import:P1-13")
      (libsource (lib "eagle-import") (part "TPSPAD1-1.5MM"))
    )
    (comp (ref "TP43")
      (value "TPSPAD1-1.5MM")
      (footprint "eagle-import:P1-13")
      (libsource (lib "eagle-import") (part "TPSPAD1-1.5MM"))
    )
    (comp (ref "TP44")
      (value "TPSPAD1-1.5MM")
      (footprint "eagle-import:P1-13")
      (libsource (lib "eagle-import") (part "TPSPAD1-1.5MM"))
    )
    (comp (ref "VI-SW")
      (value "TPSPAD1-1.5MM")
      (footprint "eagle-import:P1-13")
      (libsource (lib "eagle-import") (part "TPSPAD1-1.5MM"))
    )
    (comp (ref "VI-WS")
      (value "TPSPAD1-1.5MM")
      (footprint "eagle-import:P1-13")
      (libsource (lib "eagle-import") (part "TPSPAD1-1.5MM"))
    )
    (comp (ref "WARNLAMPE_SW4")
      (value "TLLY4400")
      (footprint "eagle-import:LED3MM")
      (fields (field (name "MF") "VISHAY SEMICONDUCTOR"))
      (libsource (lib "eagle-import") (part "TLLY4400"))
    )
    (comp (ref "WS")
      (value "TPSPAD1-1.5MM")
      (footprint "eagle-import:P1-13")
      (libsource (lib "eagle-import") (part "TPSPAD1-1.5MM"))
    )
    (comp (ref "WS-BL")
      (value "TPSPAD1-1.5MM")
      (footprint "eagle-import:P1-13")
      (libsource (lib "eagle-import") (part "TPSPAD1-1.5MM"))
    )
    (comp (ref "WS_")
      (value "TPSPAD1-1.5MM")
      (footprint "eagle-import:P1-13")
      (libsource (lib "eagle-import") (part "TPSPAD1-1.5MM"))
    )
    (comp (ref "ZüNDUNGSPLUS")
      (value "TLLY4400")
      (footprint "eagle-import:LED3MM")
      (fields (field (name "MF") "VISHAY SEMICONDUCTOR"))
      (libsource (lib "eagle-import") (part "TLLY4400"))
    )
    (comp (ref "öLDRUCK_SW2")
      (value "TLLY4400")
      (footprint "eagle-import:LED3MM")
      (fields (field (name "MF") "VISHAY SEMICONDUCTOR"))
      (libsource (lib "eagle-import") (part "TLLY4400"))
    )
  )
  (nets
    (net (code "1") (name "+12V") (class "Default")
      (node (ref "2") (pin "1") (pinfunction "KL_1") (pintype "passive"))
      (node (ref "IC1") (pin "IN") (pinfunction "IN_IN") (pintype "input"))
      (node (ref "IC3") (pin "16") (pinfunction "VDD_16") (pintype "power_in"))
      (node (ref "R14") (pin "2") (pinfunction "2_2") (pintype "passive"))
      (node (ref "R23") (pin "2") (pinfunction "2_2") (pintype "passive"))
      (node (ref "R28") (pin "2") (pinfunction "2_2") (pintype "passive"))
      (node (ref "R29") (pin "2") (pinfunction "2_2") (pintype "passive"))
      (node (ref "R30") (pin "2") (pinfunction "2_2") (pintype "passive"))
      (node (ref "R31") (pin "2") (pinfunction "2_2") (pintype "passive"))
      (node (ref "R37") (pin "2") (pinfunction "2_2") (pintype "passive"))
      (node (ref "T") (pin "3") (pinfunction "E_3") (pintype "passive"))
      (node (ref "T13") (pin "3") (pinfunction "E_3") (pintype "passive"))
      (node (ref "T14") (pin "3") (pinfunction "E_3") (pintype "passive"))
      (node (ref "T3") (pin "3") (pinfunction "E_3") (pintype "passive"))
      (node (ref "TP12") (pin "TP") (pinfunction "TP_TP") (pintype "input"))
      (node (ref "X1") (pin "6") (pinfunction "6_6") (pintype "passive"))
      (node (ref "X3") (pin "1") (pinfunction "S_1") (pintype "passive"))
      (node (ref "X4") (pin "1") (pinfunction "S_1") (pintype "passive"))
    )
    (net (code "2") (name "GND") (class "Default")
      (node (ref "1") (pin "12") (pinfunction "KL_12") (pintype "passive"))
      (node (ref "2") (pin "12") (pinfunction "KL_12") (pintype "passive"))
      (node (ref "BR") (pin "TP") (pinfunction "PP_TP") (pintype "input"))
      (node (ref "BR_") (pin "TP") (pinfunction "PP_TP") (pintype "input"))
      (node (ref "C1") (pin "2") (pinfunction "2_2") (pintype "passive"))
      (node (ref "C1B") (pin "2") (pinfunction "2_2") (pintype "passive"))
      (node (ref "C2") (pin "2") (pinfunction "2_2") (pintype "passive"))
      (node (ref "C3") (pin "2") (pinfunction "2_2") (pintype "passive"))
      (node (ref "C4") (pin "2") (pinfunction "2_2") (pintype "passive"))
      (node (ref "C6") (pin "2") (pinfunction "2_2") (pintype "passive"))
      (node (ref "C7") (pin "2") (pinfunction "2_2") (pintype "passive"))
      (node (ref "D9") (pin "A") (pinfunction "A_A") (pintype "passive"))
      (node (ref "GND_") (pin "TP") (pinfunction "PP_TP") (pintype "input"))
      (node (ref "IC1") (pin "GND") (pinfunction "GND_GND") (pintype "input"))
      (node (ref "IC2") (pin "4") (pinfunction "V-_4") (pintype "power_in"))
      (node (ref "IC3") (pin "11") (pinfunction "D_11") (pintype "input"))
      (node (ref "IC3") (pin "8") (pinfunction "VSS_8") (pintype "power_in"))
      (node (ref "IC5") (pin "4") (pinfunction "V-_4") (pintype "power_in"))
      (node (ref "IC6") (pin "8") (pinfunction "VSS_8") (pintype "power_in"))
      (node (ref "IC7") (pin "1") (pinfunction "GND_1") (pintype "power_in"))
      (node (ref "IC8") (pin "3") (pinfunction "GND_3") (pintype "power_in"))
      (node (ref "R11") (pin "2") (pinfunction "2_2") (pintype "passive"))
      (node (ref "R16") (pin "1") (pinfunction "1_1") (pintype "passive"))
      (node (ref "R2") (pin "1") (pinfunction "1_1") (pintype "passive"))
      (node (ref "R20") (pin "2") (pinfunction "2_2") (pintype "passive"))
      (node (ref "R22") (pin "2") (pinfunction "2_2") (pintype "passive"))
      (node (ref "R38") (pin "1") (pinfunction "1_1") (pintype "passive"))
      (node (ref "R39") (pin "1") (pinfunction "1_1") (pintype "passive"))
      (node (ref "R4") (pin "2") (pinfunction "2_2") (pintype "passive"))
      (node (ref "R41") (pin "2") (pinfunction "2_2") (pintype "passive"))
      (node (ref "R42") (pin "2") (pinfunction "2_2") (pintype "passive"))
      (node (ref "R43") (pin "2") (pinfunction "2_2") (pintype "passive"))
      (node (ref "R44") (pin "2") (pinfunction "2_2") (pintype "passive"))
      (node (ref "R45") (pin "2") (pinfunction "2_2") (pintype "passive"))
      (node (ref "R50") (pin "1") (pinfunction "1_1") (pintype "passive"))
      (node (ref "R55") (pin "1") (pinfunction "1_1") (pintype "passive"))
      (node (ref "R69") (pin "2") (pinfunction "2_2") (pintype "passive"))
      (node (ref "R8") (pin "1") (pinfunction "1_1") (pintype "passive"))
      (node (ref "S1") (pin "1") (pinfunction "S_1") (pintype "passive"))
      (node (ref "S2") (pin "1") (pinfunction "S_1") (pintype "passive"))
      (node (ref "S3") (pin "1") (pinfunction "S_1") (pintype "passive"))
      (node (ref "S4") (pin "1") (pinfunction "S_1") (pintype "passive"))
      (node (ref "START/NEUTRAL") (pin "K") (pinfunction "C_K") (pintype "passive"))
      (node (ref "T1") (pin "E") (pinfunction "E_E") (pintype "passive"))
      (node (ref "T10") (pin "E") (pinfunction "E_E") (pintype "passive"))
      (node (ref "T11") (pin "E") (pinfunction "E_E") (pintype "passive"))
      (node (ref "T12") (pin "E") (pinfunction "E_E") (pintype "passive"))
      (node (ref "T17") (pin "E") (pinfunction "E_E") (pintype "passive"))
      (node (ref "T2") (pin "E") (pinfunction "E_E") (pintype "passive"))
      (node (ref "T4") (pin "E") (pinfunction "E_E") (pintype "passive"))
      (node (ref "T5") (pin "E") (pinfunction "E_E") (pintype "passive"))
      (node (ref "T6") (pin "E") (pinfunction "E_E") (pintype "passive"))
      (node (ref "T7") (pin "E") (pinfunction "E_E") (pintype "passive"))
      (node (ref "T8") (pin "E") (pinfunction "E_E") (pintype "passive"))
      (node (ref "T9") (pin "E") (pinfunction "E_E") (pintype "passive"))
      (node (ref "X1") (pin "13") (pinfunction "13_13") (pintype "passive"))
      (node (ref "X1") (pin "18") (pinfunction "18_18") (pintype "passive"))
      (node (ref "X1") (pin "23") (pinfunction "23_23") (pintype "passive"))
      (node (ref "X2") (pin "2") (pinfunction "S_2") (pintype "passive"))
      (node (ref "X3") (pin "5") (pinfunction "S_5") (pintype "passive"))
      (node (ref "X4") (pin "5") (pinfunction "S_5") (pintype "passive"))
    )
    (net (code "3") (name "Net-(1A-KL)") (class "Default")
      (node (ref "1") (pin "1") (pinfunction "KL_1") (pintype "passive"))
      (node (ref "TP1") (pin "TP") (pinfunction "TP_TP") (pintype "input"))
      (node (ref "X1") (pin "1") (pinfunction "1_1") (pintype "passive"))
    )
    (net (code "4") (name "Net-(1B-KL)") (class "Default")
      (node (ref "1") (pin "10") (pinfunction "KL_10") (pintype "passive"))
      (node (ref "D1") (pin "K") (pinfunction "C_K") (pintype "passive"))
      (node (ref "D2") (pin "K") (pinfunction "C_K") (pintype "passive"))
      (node (ref "TP10") (pin "TP") (pinfunction "TP_TP") (pintype "input"))
    )
    (net (code "5") (name "Net-(1C-KL)") (class "Default")
      (node (ref "1") (pin "11") (pinfunction "KL_11") (pintype "passive"))
      (node (ref "D2") (pin "A") (pinfunction "A_A") (pintype "passive"))
      (node (ref "TP11") (pin "TP") (pinfunction "TP_TP") (pintype "input"))
      (node (ref "X1") (pin "19") (pinfunction "19_19") (pintype "passive"))
    )
    (net (code "6") (name "Net-(1E-KL)") (class "Default")
      (node (ref "1") (pin "2") (pinfunction "KL_2") (pintype "passive"))
      (node (ref "T14") (pin "2") (pinfunction "C_2") (pintype "passive"))
      (node (ref "TP2") (pin "TP") (pinfunction "TP_TP") (pintype "input"))
    )
    (net (code "7") (name "Net-(1F-KL)") (class "Default")
      (node (ref "1") (pin "3") (pinfunction "KL_3") (pintype "passive"))
      (node (ref "T12") (pin "C") (pinfunction "C_C") (pintype "passive"))
      (node (ref "TP3") (pin "TP") (pinfunction "TP_TP") (pintype "input"))
    )
    (net (code "8") (name "Net-(1G-KL)") (class "Default")
      (node (ref "1") (pin "4") (pinfunction "KL_4") (pintype "passive"))
      (node (ref "T11") (pin "C") (pinfunction "C_C") (pintype "passive"))
      (node (ref "TP4") (pin "TP") (pinfunction "TP_TP") (pintype "input"))
    )
    (net (code "9") (name "Net-(1H-KL)") (class "Default")
      (node (ref "1") (pin "5") (pinfunction "KL_5") (pintype "passive"))
      (node (ref "T10") (pin "C") (pinfunction "C_C") (pintype "passive"))
      (node (ref "TP5") (pin "TP") (pinfunction "TP_TP") (pintype "input"))
    )
    (net (code "10") (name "Net-(1I-KL)") (class "Default")
      (node (ref "1") (pin "6") (pinfunction "KL_6") (pintype "passive"))
      (node (ref "T9") (pin "C") (pinfunction "C_C") (pintype "passive"))
      (node (ref "TP6") (pin "TP") (pinfunction "TP_TP") (pintype "input"))
    )
    (net (code "11") (name "Net-(1J-KL)") (class "Default")
      (node (ref "1") (pin "7") (pinfunction "KL_7") (pintype "passive"))
      (node (ref "T8") (pin "C") (pinfunction "C_C") (pintype "passive"))
      (node (ref "TP7") (pin "TP") (pinfunction "TP_TP") (pintype "input"))
    )
    (net (code "12") (name "Net-(1K-KL)") (class "Default")
      (node (ref "1") (pin "8") (pinfunction "KL_8") (pintype "passive"))
      (node (ref "T7") (pin "C") (pinfunction "C_C") (pintype "passive"))
      (node (ref "TP8") (pin "TP") (pinfunction "TP_TP") (pintype "input"))
    )
    (net (code "13") (name "Net-(1L-KL)") (class "Default")
      (node (ref "1") (pin "9") (pinfunction "KL_9") (pintype "passive"))
      (node (ref "D1") (pin "A") (pinfunction "A_A") (pintype "passive"))
      (node (ref "TP9") (pin "TP") (pinfunction "TP_TP") (pintype "input"))
      (node (ref "X1") (pin "17") (pinfunction "17_17") (pintype "passive"))
    )
    (net (code "14") (name "Net-(2B-KL)") (class "Default")
      (node (ref "2") (pin "10") (pinfunction "KL_10") (pintype "passive"))
      (node (ref "TP25") (pin "TP") (pinfunction "TP_TP") (pintype "input"))
      (node (ref "X1") (pin "15") (pinfunction "15_15") (pintype "passive"))
    )
    (net (code "15") (name "Net-(2C-KL)") (class "Default")
      (node (ref "2") (pin "11") (pinfunction "KL_11") (pintype "passive"))
      (node (ref "T1") (pin "C") (pinfunction "C_C") (pintype "passive"))
      (node (ref "TP26") (pin "TP") (pinfunction "TP_TP") (pintype "input"))
      (node (ref "X1") (pin "21") (pinfunction "21_21") (pintype "passive"))
    )
    (net (code "16") (name "Net-(2E-KL)") (class "Default")
      (node (ref "2") (pin "2") (pinfunction "KL_2") (pintype "passive"))
      (node (ref "D6") (pin "K") (pinfunction "C_K") (pintype "passive"))
      (node (ref "TP16") (pin "TP") (pinfunction "TP_TP") (pintype "input"))
      (node (ref "X1") (pin "12") (pinfunction "12_12") (pintype "passive"))
    )
    (net (code "17") (name "Net-(2F-KL)") (class "Default")
      (node (ref "2") (pin "3") (pinfunction "KL_3") (pintype "passive"))
      (node (ref "D5") (pin "K") (pinfunction "C_K") (pintype "passive"))
      (node (ref "TP17") (pin "TP") (pinfunction "TP_TP") (pintype "input"))
      (node (ref "X1") (pin "11") (pinfunction "11_11") (pintype "passive"))
    )
    (net (code "18") (name "Net-(2G-KL)") (class "Default")
      (node (ref "2") (pin "4") (pinfunction "KL_4") (pintype "passive"))
      (node (ref "D4") (pin "K") (pinfunction "C_K") (pintype "passive"))
      (node (ref "TP18") (pin "TP") (pinfunction "TP_TP") (pintype "input"))
      (node (ref "X1") (pin "10") (pinfunction "10_10") (pintype "passive"))
    )
    (net (code "19") (name "Net-(2H-KL)") (class "Default")
      (node (ref "2") (pin "5") (pinfunction "KL_5") (pintype "passive"))
      (node (ref "D3") (pin "K") (pinfunction "C_K") (pintype "passive"))
      (node (ref "TP19") (pin "TP") (pinfunction "TP_TP") (pintype "input"))
      (node (ref "X1") (pin "9") (pinfunction "9_9") (pintype "passive"))
    )
    (net (code "20") (name "Net-(2I-KL)") (class "Default")
      (node (ref "2") (pin "6") (pinfunction "KL_6") (pintype "passive"))
      (node (ref "T5") (pin "C") (pinfunction "C_C") (pintype "passive"))
      (node (ref "TP21") (pin "TP") (pinfunction "TP_TP") (pintype "input"))
    )
    (net (code "21") (name "Net-(2J-KL)") (class "Default")
      (node (ref "2") (pin "7") (pinfunction "KL_7") (pintype "passive"))
      (node (ref "TP22") (pin "TP") (pinfunction "TP_TP") (pintype "input"))
      (node (ref "X1") (pin "8") (pinfunction "8_8") (pintype "passive"))
    )
    (net (code "22") (name "Net-(2K-KL)") (class "Default")
      (node (ref "2") (pin "8") (pinfunction "KL_8") (pintype "passive"))
      (node (ref "D7") (pin "K") (pinfunction "C_K") (pintype "passive"))
      (node (ref "TP23") (pin "TP") (pinfunction "TP_TP") (pintype "input"))
      (node (ref "X1") (pin "14") (pinfunction "14_14") (pintype "passive"))
    )
    (net (code "23") (name "Net-(2L-KL)") (class "Default")
      (node (ref "2") (pin "9") (pinfunction "KL_9") (pintype "passive"))
      (node (ref "D4") (pin "A") (pinfunction "A_A") (pintype "passive"))
      (node (ref "D5") (pin "A") (pinfunction "A_A") (pintype "passive"))
      (node (ref "D6") (pin "A") (pinfunction "A_A") (pintype "passive"))
      (node (ref "D7") (pin "A") (pinfunction "A_A") (pintype "passive"))
      (node (ref "TP24") (pin "TP") (pinfunction "TP_TP") (pintype "input"))
    )
    (net (code "24") (name "Net-(ABS_BLINK-C)") (class "Default")
      (node (ref "ABS_BLINK") (pin "K") (pinfunction "C_K") (pintype "passive"))
      (node (ref "TP40") (pin "TP") (pinfunction "PP_TP") (pintype "input"))
    )
    (net (code "25") (name "Net-(BEIDE-C)") (class "Default")
      (node (ref "BEIDE") (pin "K") (pinfunction "C_K") (pintype "passive"))
      (node (ref "R42") (pin "1") (pinfunction "1_1") (pintype "passive"))
    )
    (net (code "26") (name "Net-(BL-GR-PP)") (class "Default")
      (node (ref "BL-GR") (pin "TP") (pinfunction "PP_TP") (pintype "input"))
      (node (ref "R52") (pin "2") (pinfunction "2_2") (pintype "passive"))
    )
    (net (code "27") (name "Net-(BL-PP)") (class "Default")
      (node (ref "BL") (pin "TP") (pinfunction "PP_TP") (pintype "input"))
      (node (ref "R54") (pin "1") (pinfunction "1_1") (pintype "passive"))
    )
    (net (code "28") (name "Net-(BL-RT-PP)") (class "Default")
      (node (ref "BL-RT") (pin "TP") (pinfunction "PP_TP") (pintype "input"))
      (node (ref "T16") (pin "E") (pinfunction "E_E") (pintype "passive"))
    )
    (net (code "29") (name "Net-(BL-SW-PP)") (class "Default")
      (node (ref "BL-SW") (pin "TP") (pinfunction "PP_TP") (pintype "input"))
      (node (ref "T15") (pin "E") (pinfunction "E_E") (pintype "passive"))
    )
    (net (code "30") (name "Net-(BR-GR-PP)") (class "Default")
      (node (ref "BR-GR") (pin "TP") (pinfunction "PP_TP") (pintype "input"))
      (node (ref "R60") (pin "1") (pinfunction "1_1") (pintype "passive"))
      (node (ref "R61") (pin "1") (pinfunction "1_1") (pintype "passive"))
      (node (ref "R62") (pin "2") (pinfunction "2_2") (pintype "passive"))
      (node (ref "S2") (pin "3") (pinfunction "P_3") (pintype "passive"))
    )
    (net (code "31") (name "Net-(BR-SW-PP)") (class "Default")
      (node (ref "BR-SW") (pin "TP") (pinfunction "PP_TP") (pintype "input"))
      (node (ref "R60") (pin "2") (pinfunction "2_2") (pintype "passive"))
      (node (ref "S3") (pin "3") (pinfunction "P_3") (pintype "passive"))
    )
    (net (code "32") (name "Net-(C2-Pad1)") (class "Default")
      (node (ref "C2") (pin "1") (pinfunction "1_1") (pintype "passive"))
      (node (ref "R10") (pin "1") (pinfunction "1_1") (pintype "passive"))
      (node (ref "R12") (pin "2") (pinfunction "2_2") (pintype "passive"))
    )
    (net (code "33") (name "Net-(C5-Pad1)") (class "Default")
      (node (ref "C5") (pin "1") (pinfunction "1_1") (pintype "passive"))
      (node (ref "R50") (pin "2") (pinfunction "2_2") (pintype "passive"))
      (node (ref "R51") (pin "2") (pinfunction "2_2") (pintype "passive"))
    )
    (net (code "34") (name "Net-(CHOKE_SW1-C)") (class "Default")
      (node (ref "CHOKE_SW1") (pin "K") (pinfunction "C_K") (pintype "passive"))
      (node (ref "R63") (pin "2") (pinfunction "2_2") (pintype "passive"))
    )
    (net (code "35") (name "Net-(D3-PadA)") (class "Default")
      (node (ref "D3") (pin "A") (pinfunction "A_A") (pintype "passive"))
      (node (ref "R27") (pin "1") (pinfunction "1_1") (pintype "passive"))
    )
    (net (code "36") (name "Net-(D9-C)") (class "Default")
      (node (ref "D9") (pin "K") (pinfunction "C_K") (pintype "passive"))
      (node (ref "T") (pin "2") (pinfunction "C_2") (pintype "passive"))
      (node (ref "X1") (pin "5") (pinfunction "5_5") (pintype "passive"))
    )
    (net (code "37") (name "Net-(DAUERPLUS-C)") (class "Default")
      (node (ref "DAUERPLUS") (pin "K") (pinfunction "C_K") (pintype "passive"))
      (node (ref "R44") (pin "1") (pinfunction "1_1") (pintype "passive"))
    )
    (net (code "38") (name "Net-(FERNLICHT_BLK-C)") (class "Default")
      (node (ref "FERNLICHT_BLK") (pin "K") (pinfunction "C_K") (pintype "passive"))
      (node (ref "TP43") (pin "TP") (pinfunction "PP_TP") (pintype "input"))
    )
    (net (code "39") (name "Net-(GANG_1-C)") (class "Default")
      (node (ref "GANG_1") (pin "K") (pinfunction "C_K") (pintype "passive"))
      (node (ref "TP15") (pin "TP") (pinfunction "PP_TP") (pintype "input"))
    )
    (net (code "40") (name "Net-(GANG_2-C)") (class "Default")
      (node (ref "GANG_2") (pin "K") (pinfunction "C_K") (pintype "passive"))
      (node (ref "TP20") (pin "TP") (pinfunction "PP_TP") (pintype "input"))
    )
    (net (code "41") (name "Net-(GANG_3-C)") (class "Default")
      (node (ref "GANG_3") (pin "K") (pinfunction "C_K") (pintype "passive"))
      (node (ref "TP27") (pin "TP") (pinfunction "PP_TP") (pintype "input"))
    )
    (net (code "42") (name "Net-(GANG_4-C)") (class "Default")
      (node (ref "GANG_4") (pin "K") (pinfunction "C_K") (pintype "passive"))
      (node (ref "TP28") (pin "TP") (pinfunction "PP_TP") (pintype "input"))
    )
    (net (code "43") (name "Net-(GANG_5-C)") (class "Default")
      (node (ref "GANG_5") (pin "K") (pinfunction "C_K") (pintype "passive"))
      (node (ref "TP29") (pin "TP") (pinfunction "PP_TP") (pintype "input"))
    )
    (net (code "44") (name "Net-(GB-SW-PP)") (class "Default")
      (node (ref "GB-SW") (pin "TP") (pinfunction "PP_TP") (pintype "input"))
      (node (ref "IC6") (pin "2") (pinfunction "Q13_2") (pintype "output"))
      (node (ref "R47") (pin "2") (pinfunction "2_2") (pintype "passive"))
    )
    (net (code "45") (name "Net-(GB-WS-PP)") (class "Default")
      (node (ref "GB-WS") (pin "TP") (pinfunction "PP_TP") (pintype "input"))
      (node (ref "IC6") (pin "3") (pinfunction "Q14_3") (pintype "output"))
    )
    (net (code "46") (name "Net-(GE-BL-PP)") (class "Default")
      (node (ref "GE-BL") (pin "TP") (pinfunction "PP_TP") (pintype "input"))
      (node (ref "IC6") (pin "1") (pinfunction "Q12_1") (pintype "output"))
      (node (ref "R48") (pin "2") (pinfunction "2_2") (pintype "passive"))
      (node (ref "R49") (pin "2") (pinfunction "2_2") (pintype "passive"))
      (node (ref "R51") (pin "1") (pinfunction "1_1") (pintype "passive"))
    )
    (net (code "47") (name "Net-(GESCHW_WAGO_BLK-C)") (class "Default")
      (node (ref "GESCHW_WAGO_BLK") (pin "K") (pinfunction "C_K") (pintype "passive"))
      (node (ref "TP44") (pin "TP") (pinfunction "PP_TP") (pintype "input"))
    )
    (net (code "48") (name "Net-(GESCHW_WAGO_BLK-PadA)") (class "Default")
      (node (ref "GESCHW_WAGO_BLK") (pin "A") (pinfunction "A_A") (pintype "passive"))
      (node (ref "R59") (pin "1") (pinfunction "1_1") (pintype "passive"))
    )
    (net (code "49") (name "Net-(GR-PP)") (class "Default")
      (node (ref "C5") (pin "2") (pinfunction "2_2") (pintype "passive"))
      (node (ref "GR") (pin "TP") (pinfunction "PP_TP") (pintype "input"))
    )
    (net (code "50") (name "Net-(IC2A-+IN)") (class "Default")
      (node (ref "C1") (pin "1") (pinfunction "1_1") (pintype "passive"))
      (node (ref "C1B") (pin "1") (pinfunction "1_1") (pintype "passive"))
      (node (ref "IC2") (pin "3") (pinfunction "+IN_3") (pintype "input"))
      (node (ref "R1") (pin "1") (pinfunction "1_1") (pintype "passive"))
    )
    (net (code "51") (name "Net-(IC2A--IN)") (class "Default")
      (node (ref "IC2") (pin "2") (pinfunction "-IN_2") (pintype "input"))
      (node (ref "R2") (pin "2") (pinfunction "2_2") (pintype "passive"))
    )
    (net (code "52") (name "Net-(IC2A-OUT)") (class "Default")
      (node (ref "IC2") (pin "1") (pinfunction "OUT_1") (pintype "output"))
      (node (ref "R3") (pin "2") (pinfunction "2_2") (pintype "passive"))
    )
    (net (code "53") (name "Net-(IC2B-+IN)") (class "Default")
      (node (ref "IC2") (pin "5") (pinfunction "+IN_5") (pintype "input"))
      (node (ref "R6") (pin "1") (pinfunction "1_1") (pintype "passive"))
      (node (ref "R7") (pin "2") (pinfunction "2_2") (pintype "passive"))
    )
    (net (code "54") (name "Net-(IC2B--IN)") (class "Default")
      (node (ref "IC2") (pin "6") (pinfunction "-IN_6") (pintype "input"))
      (node (ref "IC5") (pin "5") (pinfunction "+IN_5") (pintype "input"))
      (node (ref "R5") (pin "1") (pinfunction "1_1") (pintype "passive"))
    )
    (net (code "55") (name "Net-(IC2B-OUT)") (class "Default")
      (node (ref "IC2") (pin "7") (pinfunction "OUT_7") (pintype "output"))
      (node (ref "R10") (pin "2") (pinfunction "2_2") (pintype "passive"))
    )
    (net (code "56") (name "Net-(IC3A-A)") (class "Default")
      (node (ref "IC3") (pin "10") (pinfunction "A_10") (pintype "input"))
      (node (ref "R31") (pin "1") (pinfunction "1_1") (pintype "passive"))
      (node (ref "X1") (pin "4") (pinfunction "4_4") (pintype "passive"))
      (node (ref "X3") (pin "2") (pinfunction "S_2") (pintype "passive"))
      (node (ref "X4") (pin "2") (pinfunction "S_2") (pintype "passive"))
    )
    (net (code "57") (name "Net-(IC3A-B)") (class "Default")
      (node (ref "IC3") (pin "13") (pinfunction "B_13") (pintype "input"))
      (node (ref "R30") (pin "1") (pinfunction "1_1") (pintype "passive"))
      (node (ref "X1") (pin "3") (pinfunction "3_3") (pintype "passive"))
      (node (ref "X3") (pin "3") (pinfunction "S_3") (pintype "passive"))
      (node (ref "X4") (pin "3") (pinfunction "S_3") (pintype "passive"))
    )
    (net (code "58") (name "Net-(IC3A-C)") (class "Default")
      (node (ref "IC3") (pin "12") (pinfunction "C_12") (pintype "input"))
      (node (ref "R29") (pin "1") (pinfunction "1_1") (pintype "passive"))
      (node (ref "X1") (pin "2") (pinfunction "2_2") (pintype "passive"))
      (node (ref "X3") (pin "4") (pinfunction "S_4") (pintype "passive"))
      (node (ref "X4") (pin "4") (pinfunction "S_4") (pintype "passive"))
    )
    (net (code "59") (name "Net-(IC3A-Q0)") (class "Default")
      (node (ref "IC3") (pin "3") (pinfunction "Q0_3") (pintype "output"))
      (node (ref "R25") (pin "2") (pinfunction "2_2") (pintype "passive"))
      (node (ref "R26") (pin "2") (pinfunction "2_2") (pintype "passive"))
    )
    (net (code "60") (name "Net-(IC3A-Q1)") (class "Default")
      (node (ref "IC3") (pin "14") (pinfunction "Q1_14") (pintype "output"))
      (node (ref "R36") (pin "2") (pinfunction "2_2") (pintype "passive"))
    )
    (net (code "61") (name "Net-(IC3A-Q2)") (class "Default")
      (node (ref "IC3") (pin "2") (pinfunction "Q2_2") (pintype "output"))
      (node (ref "R35") (pin "2") (pinfunction "2_2") (pintype "passive"))
    )
    (net (code "62") (name "Net-(IC3A-Q3)") (class "Default")
      (node (ref "IC3") (pin "15") (pinfunction "Q3_15") (pintype "output"))
      (node (ref "R34") (pin "2") (pinfunction "2_2") (pintype "passive"))
    )
    (net (code "63") (name "Net-(IC3A-Q4)") (class "Default")
      (node (ref "IC3") (pin "1") (pinfunction "Q4_1") (pintype "output"))
      (node (ref "R33") (pin "2") (pinfunction "2_2") (pintype "passive"))
    )
    (net (code "64") (name "Net-(IC3A-Q5)") (class "Default")
      (node (ref "IC3") (pin "6") (pinfunction "Q5_6") (pintype "output"))
      (node (ref "R32") (pin "2") (pinfunction "2_2") (pintype "passive"))
    )
    (net (code "65") (name "Net-(IC4-ADJ)") (class "Default")
      (node (ref "IC4") (pin "1") (pinfunction "ADJ_1") (pintype "input"))
      (node (ref "R18") (pin "1") (pinfunction "1_1") (pintype "passive"))
      (node (ref "R5") (pin "2") (pinfunction "2_2") (pintype "passive"))
      (node (ref "X1") (pin "7") (pinfunction "7_7") (pintype "passive"))
    )
    (net (code "66") (name "Net-(IC4-VI)") (class "Default")
      (node (ref "IC4") (pin "3") (pinfunction "VI_3") (pintype "input"))
      (node (ref "R37") (pin "1") (pinfunction "1_1") (pintype "passive"))
      (node (ref "T3") (pin "2") (pinfunction "C_2") (pintype "passive"))
    )
    (net (code "67") (name "Net-(IC4-VO)") (class "Default")
      (node (ref "IC4") (pin "2") (pinfunction "VO_2") (pintype "passive"))
      (node (ref "R18") (pin "2") (pinfunction "2_2") (pintype "passive"))
    )
    (net (code "68") (name "Net-(IC5A-+IN)") (class "Default")
      (node (ref "C3") (pin "1") (pinfunction "1_1") (pintype "passive"))
      (node (ref "IC5") (pin "3") (pinfunction "+IN_3") (pintype "input"))
      (node (ref "R12") (pin "1") (pinfunction "1_1") (pintype "passive"))
    )
    (net (code "69") (name "Net-(IC5A--IN)") (class "Default")
      (node (ref "IC5") (pin "2") (pinfunction "-IN_2") (pintype "input"))
      (node (ref "R15") (pin "1") (pinfunction "1_1") (pintype "passive"))
      (node (ref "R16") (pin "2") (pinfunction "2_2") (pintype "passive"))
      (node (ref "R17") (pin "2") (pinfunction "2_2") (pintype "passive"))
    )
    (net (code "70") (name "Net-(IC5A-OUT)") (class "Default")
      (node (ref "IC5") (pin "1") (pinfunction "OUT_1") (pintype "output"))
      (node (ref "R19") (pin "2") (pinfunction "2_2") (pintype "passive"))
      (node (ref "R21") (pin "2") (pinfunction "2_2") (pintype "passive"))
    )
    (net (code "71") (name "Net-(IC5B--IN)") (class "Default")
      (node (ref "IC5") (pin "6") (pinfunction "-IN_6") (pintype "input"))
      (node (ref "R7") (pin "1") (pinfunction "1_1") (pintype "passive"))
      (node (ref "R8") (pin "2") (pinfunction "2_2") (pintype "passive"))
    )
    (net (code "72") (name "Net-(IC5B-OUT)") (class "Default")
      (node (ref "IC5") (pin "7") (pinfunction "OUT_7") (pintype "output"))
      (node (ref "R9") (pin "2") (pinfunction "2_2") (pintype "passive"))
    )
    (net (code "73") (name "Net-(IC6A-P1)") (class "Default")
      (node (ref "IC6") (pin "10") (pinfunction "P1_10") (pintype "input"))
      (node (ref "IC7") (pin "3") (pinfunction "OUT_3") (pintype "output"))
    )
    (net (code "74") (name "Net-(IC6A-RES)") (class "Default")
      (node (ref "IC6") (pin "11") (pinfunction "RES_11") (pintype "input"))
      (node (ref "R69") (pin "1") (pinfunction "1_1") (pintype "passive"))
    )
    (net (code "75") (name "Net-(IC7-CON)") (class "Default")
      (node (ref "C7") (pin "1") (pinfunction "1_1") (pintype "passive"))
      (node (ref "IC7") (pin "5") (pinfunction "CON_5") (pintype "input"))
    )
    (net (code "76") (name "Net-(IC7-DIS)") (class "Default")
      (node (ref "IC7") (pin "7") (pinfunction "DIS_7") (pintype "input"))
      (node (ref "R67") (pin "1") (pinfunction "1_1") (pintype "passive"))
      (node (ref "R68") (pin "2") (pinfunction "2_2") (pintype "passive"))
    )
    (net (code "77") (name "Net-(IC7-TRE)") (class "Default")
      (node (ref "C6") (pin "1") (pinfunction "1_1") (pintype "passive"))
      (node (ref "IC7") (pin "2") (pinfunction "TRI_2") (pintype "input"))
      (node (ref "IC7") (pin "6") (pinfunction "TRE_6") (pintype "input"))
      (node (ref "R68") (pin "1") (pinfunction "1_1") (pintype "passive"))
    )
    (net (code "78") (name "Net-(IC8-IN)") (class "Default")
      (node (ref "IC8") (pin "1") (pinfunction "IN_1") (pintype "input"))
      (node (ref "R53") (pin "2") (pinfunction "2_2") (pintype "passive"))
      (node (ref "R54") (pin "2") (pinfunction "2_2") (pintype "passive"))
      (node (ref "R56") (pin "1") (pinfunction "1_1") (pintype "passive"))
      (node (ref "T17") (pin "C") (pinfunction "C_C") (pintype "passive"))
    )
    (net (code "79") (name "Net-(IC8-OUT)") (class "Default")
      (node (ref "IC8") (pin "2") (pinfunction "OUT_2") (pintype "output"))
      (node (ref "VI-SW") (pin "TP") (pinfunction "PP_TP") (pintype "input"))
    )
    (net (code "80") (name "Net-(LADEKONTROL_BLK-C)") (class "Default")
      (node (ref "LADEKONTROL_BLK") (pin "K") (pinfunction "C_K") (pintype "passive"))
      (node (ref "TP38") (pin "TP") (pinfunction "PP_TP") (pintype "input"))
    )
    (net (code "81") (name "Net-(LADEKONTROL_BLK-PadA)") (class "Default")
      (node (ref "LADEKONTROL_BLK") (pin "A") (pinfunction "A_A") (pintype "passive"))
      (node (ref "R46") (pin "1") (pinfunction "1_1") (pintype "passive"))
    )
    (net (code "82") (name "Net-(LAMPENTEST_SW4-C)") (class "Default")
      (node (ref "LAMPENTEST_SW4") (pin "K") (pinfunction "C_K") (pintype "passive"))
      (node (ref "R57") (pin "2") (pinfunction "2_2") (pintype "passive"))
    )
    (net (code "83") (name "Net-(LINKS-C)") (class "Default")
      (node (ref "LINKS") (pin "K") (pinfunction "C_K") (pintype "passive"))
      (node (ref "R43") (pin "1") (pinfunction "1_1") (pintype "passive"))
    )
    (net (code "84") (name "Net-(NEUTRAL-C)") (class "Default")
      (node (ref "NEUTRAL") (pin "K") (pinfunction "C_K") (pintype "passive"))
      (node (ref "TP30") (pin "TP") (pinfunction "PP_TP") (pintype "input"))
    )
    (net (code "85") (name "Net-(R1-Pad2)") (class "Default")
      (node (ref "R1") (pin "2") (pinfunction "2_2") (pintype "passive"))
      (node (ref "X1") (pin "22") (pinfunction "22_22") (pintype "passive"))
    )
    (net (code "86") (name "Net-(R3-Pad1)") (class "Default")
      (node (ref "R3") (pin "1") (pinfunction "1_1") (pintype "passive"))
      (node (ref "R4") (pin "1") (pinfunction "1_1") (pintype "passive"))
      (node (ref "T1") (pin "B") (pinfunction "B_B") (pintype "passive"))
    )
    (net (code "87") (name "Net-(R11-Pad1)") (class "Default")
      (node (ref "R11") (pin "1") (pinfunction "1_1") (pintype "passive"))
      (node (ref "R9") (pin "1") (pinfunction "1_1") (pintype "passive"))
      (node (ref "T2") (pin "B") (pinfunction "B_B") (pintype "passive"))
    )
    (net (code "88") (name "Net-(R13-Pad2)") (class "Default")
      (node (ref "R13") (pin "2") (pinfunction "2_2") (pintype "passive"))
      (node (ref "T2") (pin "C") (pinfunction "C_C") (pintype "passive"))
    )
    (net (code "89") (name "Net-(R17-Pad1)") (class "Default")
      (node (ref "R17") (pin "1") (pinfunction "1_1") (pintype "passive"))
      (node (ref "T4") (pin "C") (pinfunction "C_C") (pintype "passive"))
    )
    (net (code "90") (name "Net-(R19-Pad1)") (class "Default")
      (node (ref "R19") (pin "1") (pinfunction "1_1") (pintype "passive"))
      (node (ref "R20") (pin "1") (pinfunction "1_1") (pintype "passive"))
      (node (ref "T4") (pin "B") (pinfunction "B_B") (pintype "passive"))
    )
    (net (code "91") (name "Net-(R21-Pad1)") (class "Default")
      (node (ref "R21") (pin "1") (pinfunction "1_1") (pintype "passive"))
      (node (ref "R22") (pin "1") (pinfunction "1_1") (pintype "passive"))
      (node (ref "T5") (pin "B") (pinfunction "B_B") (pintype "passive"))
    )
    (net (code "92") (name "Net-(R24-Pad1)") (class "Default")
      (node (ref "R24") (pin "1") (pinfunction "1_1") (pintype "passive"))
      (node (ref "T6") (pin "C") (pinfunction "C_C") (pintype "passive"))
    )
    (net (code "93") (name "Net-(R25-Pad1)") (class "Default")
      (node (ref "R25") (pin "1") (pinfunction "1_1") (pintype "passive"))
      (node (ref "T6") (pin "B") (pinfunction "B_B") (pintype "passive"))
    )
    (net (code "94") (name "Net-(R26-Pad1)") (class "Default")
      (node (ref "R26") (pin "1") (pinfunction "1_1") (pintype "passive"))
      (node (ref "T7") (pin "B") (pinfunction "B_B") (pintype "passive"))
    )
    (net (code "95") (name "Net-(R27-Pad2)") (class "Default")
      (node (ref "R27") (pin "2") (pinfunction "2_2") (pintype "passive"))
      (node (ref "R28") (pin "1") (pinfunction "1_1") (pintype "passive"))
    )
    (net (code "96") (name "Net-(R32-Pad1)") (class "Default")
      (node (ref "R32") (pin "1") (pinfunction "1_1") (pintype "passive"))
      (node (ref "T8") (pin "B") (pinfunction "B_B") (pintype "passive"))
    )
    (net (code "97") (name "Net-(R33-Pad1)") (class "Default")
      (node (ref "R33") (pin "1") (pinfunction "1_1") (pintype "passive"))
      (node (ref "T9") (pin "B") (pinfunction "B_B") (pintype "passive"))
    )
    (net (code "98") (name "Net-(R34-Pad1)") (class "Default")
      (node (ref "R34") (pin "1") (pinfunction "1_1") (pintype "passive"))
      (node (ref "T10") (pin "B") (pinfunction "B_B") (pintype "passive"))
    )
    (net (code "99") (name "Net-(R35-Pad1)") (class "Default")
      (node (ref "R35") (pin "1") (pinfunction "1_1") (pintype "passive"))
      (node (ref "T11") (pin "B") (pinfunction "B_B") (pintype "passive"))
    )
    (net (code "100") (name "Net-(R36-Pad1)") (class "Default")
      (node (ref "R36") (pin "1") (pinfunction "1_1") (pintype "passive"))
      (node (ref "T12") (pin "B") (pinfunction "B_B") (pintype "passive"))
    )
    (net (code "101") (name "Net-(R40-Pad2)") (class "Default")
      (node (ref "R40") (pin "2") (pinfunction "2_2") (pintype "passive"))
      (node (ref "START/NEUTRAL") (pin "A") (pinfunction "A_A") (pintype "passive"))
    )
    (net (code "102") (name "Net-(R47-Pad1)") (class "Default")
      (node (ref "R47") (pin "1") (pinfunction "1_1") (pintype "passive"))
      (node (ref "T15") (pin "B") (pinfunction "B_B") (pintype "passive"))
    )
    (net (code "103") (name "Net-(R48-Pad1)") (class "Default")
      (node (ref "R48") (pin "1") (pinfunction "1_1") (pintype "passive"))
      (node (ref "T16") (pin "B") (pinfunction "B_B") (pintype "passive"))
    )
    (net (code "104") (name "Net-(R49-Pad1)") (class "Default")
      (node (ref "R49") (pin "1") (pinfunction "1_1") (pintype "passive"))
      (node (ref "R55") (pin "2") (pinfunction "2_2") (pintype "passive"))
      (node (ref "T17") (pin "B") (pinfunction "B_B") (pintype "passive"))
    )
    (net (code "105") (name "Net-(RECHT-C)") (class "Default")
      (node (ref "R41") (pin "1") (pinfunction "1_1") (pintype "passive"))
      (node (ref "RECHT") (pin "K") (pinfunction "C_K") (pintype "passive"))
    )
    (net (code "106") (name "Net-(S1-P)") (class "Default")
      (node (ref "S1") (pin "3") (pinfunction "P_3") (pintype "passive"))
      (node (ref "VI-WS") (pin "TP") (pinfunction "PP_TP") (pintype "input"))
    )
    (net (code "107") (name "Net-(S4-P)") (class "Default")
      (node (ref "R61") (pin "2") (pinfunction "2_2") (pintype "passive"))
      (node (ref "S4") (pin "3") (pinfunction "P_3") (pintype "passive"))
      (node (ref "WS-BL") (pin "TP") (pinfunction "PP_TP") (pintype "input"))
    )
    (net (code "108") (name "Net-(SW-GR-PP)") (class "Default")
      (node (ref "R40") (pin "1") (pinfunction "1_1") (pintype "passive"))
      (node (ref "SW-GR") (pin "TP") (pinfunction "PP_TP") (pintype "input"))
    )
    (net (code "109") (name "Net-(T-B)") (class "Default")
      (node (ref "R23") (pin "1") (pinfunction "1_1") (pintype "passive"))
      (node (ref "R24") (pin "2") (pinfunction "2_2") (pintype "passive"))
      (node (ref "T") (pin "1") (pinfunction "B_1") (pintype "passive"))
    )
    (net (code "110") (name "Net-(T3-B)") (class "Default")
      (node (ref "R13") (pin "1") (pinfunction "1_1") (pintype "passive"))
      (node (ref "R14") (pin "1") (pinfunction "1_1") (pintype "passive"))
      (node (ref "T3") (pin "1") (pinfunction "B_1") (pintype "passive"))
    )
    (net (code "111") (name "Net-(T13-B)") (class "Default")
      (node (ref "R38") (pin "2") (pinfunction "2_2") (pintype "passive"))
      (node (ref "R39") (pin "2") (pinfunction "2_2") (pintype "passive"))
      (node (ref "T13") (pin "1") (pinfunction "B_1") (pintype "passive"))
      (node (ref "T13") (pin "2") (pinfunction "C_2") (pintype "passive"))
      (node (ref "T14") (pin "1") (pinfunction "B_1") (pintype "passive"))
      (node (ref "X2") (pin "1") (pinfunction "S_1") (pintype "passive"))
    )
    (net (code "112") (name "Net-(TACHSIG_REL_BLK-C)") (class "Default")
      (node (ref "R52") (pin "1") (pinfunction "1_1") (pintype "passive"))
      (node (ref "TACHSIG_REL_BLK") (pin "K") (pinfunction "C_K") (pintype "passive"))
    )
    (net (code "113") (name "Net-(TANKGEB_SW1-4-C)") (class "Default")
      (node (ref "R66") (pin "1") (pinfunction "1_1") (pintype "passive"))
      (node (ref "TANKGEB_SW1-4") (pin "K") (pinfunction "C_K") (pintype "passive"))
    )
    (net (code "114") (name "Net-(TEMP...SW3-C)") (class "Default")
      (node (ref "R65") (pin "2") (pinfunction "2_2") (pintype "passive"))
      (node (ref "TEMP...SW3") (pin "K") (pinfunction "C_K") (pintype "passive"))
    )
    (net (code "115") (name "Net-(TP13-PP)") (class "Default")
      (node (ref "DAUERPLUS") (pin "A") (pinfunction "A_A") (pintype "passive"))
      (node (ref "TP13") (pin "TP") (pinfunction "PP_TP") (pintype "input"))
    )
    (net (code "116") (name "Net-(TP14-PP)") (class "Default")
      (node (ref "GANG_1") (pin "A") (pinfunction "A_A") (pintype "passive"))
      (node (ref "GANG_2") (pin "A") (pinfunction "A_A") (pintype "passive"))
      (node (ref "GANG_3") (pin "A") (pinfunction "A_A") (pintype "passive"))
      (node (ref "GANG_4") (pin "A") (pinfunction "A_A") (pintype "passive"))
      (node (ref "GANG_5") (pin "A") (pinfunction "A_A") (pintype "passive"))
      (node (ref "NEUTRAL") (pin "A") (pinfunction "A_A") (pintype "passive"))
      (node (ref "TP14") (pin "TP") (pinfunction "PP_TP") (pintype "input"))
    )
    (net (code "117") (name "Net-(TP31-PP)") (class "Default")
      (node (ref "RECHT") (pin "A") (pinfunction "A_A") (pintype "passive"))
      (node (ref "TP31") (pin "TP") (pinfunction "PP_TP") (pintype "input"))
    )
    (net (code "118") (name "Net-(TP32-PP)") (class "Default")
      (node (ref "BEIDE") (pin "A") (pinfunction "A_A") (pintype "passive"))
      (node (ref "TP32") (pin "TP") (pinfunction "PP_TP") (pintype "input"))
    )
    (net (code "119") (name "Net-(TP33-PP)") (class "Default")
      (node (ref "LINKS") (pin "A") (pinfunction "A_A") (pintype "passive"))
      (node (ref "TP33") (pin "TP") (pinfunction "PP_TP") (pintype "input"))
    )
    (net (code "120") (name "Net-(TP34-PP)") (class "Default")
      (node (ref "TP34") (pin "TP") (pinfunction "PP_TP") (pintype "input"))
      (node (ref "ZüNDUNGSPLUS") (pin "A") (pinfunction "A_A") (pintype "passive"))
    )
    (net (code "121") (name "Net-(TP35-PP)") (class "Default")
      (node (ref "R63") (pin "1") (pinfunction "1_1") (pintype "passive"))
      (node (ref "TP35") (pin "TP") (pinfunction "PP_TP") (pintype "input"))
    )
    (net (code "122") (name "Net-(TP36-PP)") (class "Default")
      (node (ref "R64") (pin "1") (pinfunction "1_1") (pintype "passive"))
      (node (ref "TP36") (pin "TP") (pinfunction "PP_TP") (pintype "input"))
    )
    (net (code "123") (name "Net-(TP37-PP)") (class "Default")
      (node (ref "R65") (pin "1") (pinfunction "1_1") (pintype "passive"))
      (node (ref "TP37") (pin "TP") (pinfunction "PP_TP") (pintype "input"))
    )
    (net (code "124") (name "Net-(TP39-PP)") (class "Default")
      (node (ref "R66") (pin "2") (pinfunction "2_2") (pintype "passive"))
      (node (ref "TP39") (pin "TP") (pinfunction "PP_TP") (pintype "input"))
    )
    (net (code "125") (name "Net-(TP41-PP)") (class "Default")
      (node (ref "R57") (pin "1") (pinfunction "1_1") (pintype "passive"))
      (node (ref "TP41") (pin "TP") (pinfunction "PP_TP") (pintype "input"))
    )
    (net (code "126") (name "Net-(TP42-PP)") (class "Default")
      (node (ref "R58") (pin "1") (pinfunction "1_1") (pintype "passive"))
      (node (ref "TP42") (pin "TP") (pinfunction "PP_TP") (pintype "input"))
    )
    (net (code "127") (name "Net-(WARNLAMPE_SW4-C)") (class "Default")
      (node (ref "R58") (pin "2") (pinfunction "2_2") (pintype "passive"))
      (node (ref "WARNLAMPE_SW4") (pin "K") (pinfunction "C_K") (pintype "passive"))
    )
    (net (code "128") (name "Net-(WS-PP)") (class "Default")
      (node (ref "R53") (pin "1") (pinfunction "1_1") (pintype "passive"))
      (node (ref "WS") (pin "TP") (pinfunction "PP_TP") (pintype "input"))
    )
    (net (code "129") (name "Net-(WS_-PP)") (class "Default")
      (node (ref "R62") (pin "1") (pinfunction "1_1") (pintype "passive"))
      (node (ref "WS_") (pin "TP") (pinfunction "PP_TP") (pintype "input"))
    )
    (net (code "130") (name "Net-(ZÜNDPLUS-PP)") (class "Default")
      (node (ref "X1") (pin "24") (pinfunction "24_24") (pintype "passive"))
      (node (ref "ZÜNDPLUS") (pin "TP") (pinfunction "PP_TP") (pintype "input"))
    )
    (net (code "131") (name "Net-(ZüNDSPULE-PP)") (class "Default")
      (node (ref "X1") (pin "16") (pinfunction "16_16") (pintype "passive"))
      (node (ref "ZüNDSPULE") (pin "TP") (pinfunction "PP_TP") (pintype "input"))
    )
    (net (code "132") (name "Net-(ZüNDUNGSPLUS-C)") (class "Default")
      (node (ref "R45") (pin "1") (pinfunction "1_1") (pintype "passive"))
      (node (ref "ZüNDUNGSPLUS") (pin "K") (pinfunction "C_K") (pintype "passive"))
    )
    (net (code "133") (name "Net-(öLDRUCK_SW2-C)") (class "Default")
      (node (ref "R64") (pin "2") (pinfunction "2_2") (pintype "passive"))
      (node (ref "öLDRUCK_SW2") (pin "K") (pinfunction "C_K") (pintype "passive"))
    )
    (net (code "134") (name "VCC") (class "Default")
      (node (ref "12V") (pin "TP") (pinfunction "PP_TP") (pintype "input"))
      (node (ref "12V_") (pin "TP") (pinfunction "PP_TP") (pintype "input"))
      (node (ref "ABS_BLINK") (pin "A") (pinfunction "A_A") (pintype "passive"))
      (node (ref "C4") (pin "1") (pinfunction "1_1") (pintype "passive"))
      (node (ref "CHOKE_SW1") (pin "A") (pinfunction "A_A") (pintype "passive"))
      (node (ref "FERNLICHT_BLK") (pin "A") (pinfunction "A_A") (pintype "passive"))
      (node (ref "GR-SW") (pin "TP") (pinfunction "PP_TP") (pintype "input"))
      (node (ref "IC1") (pin "OUT") (pinfunction "OUT_OUT") (pintype "passive"))
      (node (ref "IC2") (pin "8") (pinfunction "V+_8") (pintype "power_in"))
      (node (ref "IC5") (pin "8") (pinfunction "V+_8") (pintype "power_in"))
      (node (ref "IC6") (pin "16") (pinfunction "VDD_16") (pintype "power_in"))
      (node (ref "IC7") (pin "4") (pinfunction "/RES_4") (pintype "input"))
      (node (ref "IC7") (pin "8") (pinfunction "VCC+_8") (pintype "power_in"))
      (node (ref "LAMPENTEST_SW4") (pin "A") (pinfunction "A_A") (pintype "passive"))
      (node (ref "R15") (pin "2") (pinfunction "2_2") (pintype "passive"))
      (node (ref "R46") (pin "2") (pinfunction "2_2") (pintype "passive"))
      (node (ref "R56") (pin "2") (pinfunction "2_2") (pintype "passive"))
      (node (ref "R59") (pin "2") (pinfunction "2_2") (pintype "passive"))
      (node (ref "R6") (pin "2") (pinfunction "2_2") (pintype "passive"))
      (node (ref "R67") (pin "2") (pinfunction "2_2") (pintype "passive"))
      (node (ref "T15") (pin "C") (pinfunction "C_C") (pintype "passive"))
      (node (ref "T16") (pin "C") (pinfunction "C_C") (pintype "passive"))
      (node (ref "TACHSIG_REL_BLK") (pin "A") (pinfunction "A_A") (pintype "passive"))
      (node (ref "TANKGEB_SW1-4") (pin "A") (pinfunction "A_A") (pintype "passive"))
      (node (ref "TEMP...SW3") (pin "A") (pinfunction "A_A") (pintype "passive"))
      (node (ref "WARNLAMPE_SW4") (pin "A") (pinfunction "A_A") (pintype "passive"))
      (node (ref "öLDRUCK_SW2") (pin "A") (pinfunction "A_A") (pintype "passive"))
    )
    (net (code "135") (name "unconnected-(IC3A-Q6-Pad7)") (class "Default")
      (node (ref "IC3") (pin "7") (pinfunction "Q6_7") (pintype "output"))
    )
    (net (code "136") (name "unconnected-(IC3A-Q7-Pad4)") (class "Default")
      (node (ref "IC3") (pin "4") (pinfunction "Q7_4") (pintype "output"))
    )
    (net (code "137") (name "unconnected-(IC3A-Q8-Pad9)") (class "Default")
      (node (ref "IC3") (pin "9") (pinfunction "Q8_9") (pintype "output"))
    )
    (net (code "138") (name "unconnected-(IC3A-Q9-Pad5)") (class "Default")
      (node (ref "IC3") (pin "5") (pinfunction "Q9_5") (pintype "output"))
    )
    (net (code "139") (name "unconnected-(IC6A-Q1-Pad9)") (class "Default")
      (node (ref "IC6") (pin "9") (pinfunction "Q1_9") (pintype "output"))
    )
    (net (code "140") (name "unconnected-(IC6A-Q4-Pad7)") (class "Default")
      (node (ref "IC6") (pin "7") (pinfunction "Q4_7") (pintype "output"))
    )
    (net (code "141") (name "unconnected-(IC6A-Q5-Pad5)") (class "Default")
      (node (ref "IC6") (pin "5") (pinfunction "Q5_5") (pintype "output"))
    )
    (net (code "142") (name "unconnected-(IC6A-Q6-Pad4)") (class "Default")
      (node (ref "IC6") (pin "4") (pinfunction "Q6_4") (pintype "output"))
    )
    (net (code "143") (name "unconnected-(IC6A-Q7-Pad6)") (class "Default")
      (node (ref "IC6") (pin "6") (pinfunction "Q7_6") (pintype "output"))
    )
    (net (code "144") (name "unconnected-(IC6A-Q8-Pad13)") (class "Default")
      (node (ref "IC6") (pin "13") (pinfunction "Q8_13") (pintype "output"))
    )
    (net (code "145") (name "unconnected-(IC6A-Q9-Pad12)") (class "Default")
      (node (ref "IC6") (pin "12") (pinfunction "Q9_12") (pintype "output"))
    )
    (net (code "146") (name "unconnected-(IC6A-Q10-Pad14)") (class "Default")
      (node (ref "IC6") (pin "14") (pinfunction "Q10_14") (pintype "output"))
    )
    (net (code "147") (name "unconnected-(IC6A-Q11-Pad15)") (class "Default")
      (node (ref "IC6") (pin "15") (pinfunction "Q11_15") (pintype "output"))
    )
    (net (code "148") (name "unconnected-(T-C{slash}-Pad4)") (class "Default")
      (node (ref "T") (pin "4") (pinfunction "C/_4") (pintype "passive"))
    )
    (net (code "149") (name "unconnected-(T3-C{slash}-Pad4)") (class "Default")
      (node (ref "T3") (pin "4") (pinfunction "C/_4") (pintype "passive"))
    )
    (net (code "150") (name "unconnected-(T13-C{slash}-Pad4)") (class "Default")
      (node (ref "T13") (pin "4") (pinfunction "C/_4") (pintype "passive"))
    )
    (net (code "151") (name "unconnected-(T14-C{slash}-Pad4)") (class "Default")
      (node (ref "T14") (pin "4") (pinfunction "C/_4") (pintype "passive"))
    )
    (net (code "152") (name "unconnected-(X1-Pad20)") (class "Default")
      (node (ref "X1") (pin "20") (pinfunction "20_20") (pintype "passive"))
    )
  )
)
